# Mk3_Prototype.net
KiCad netlist of a schematic drawn in EAGLE
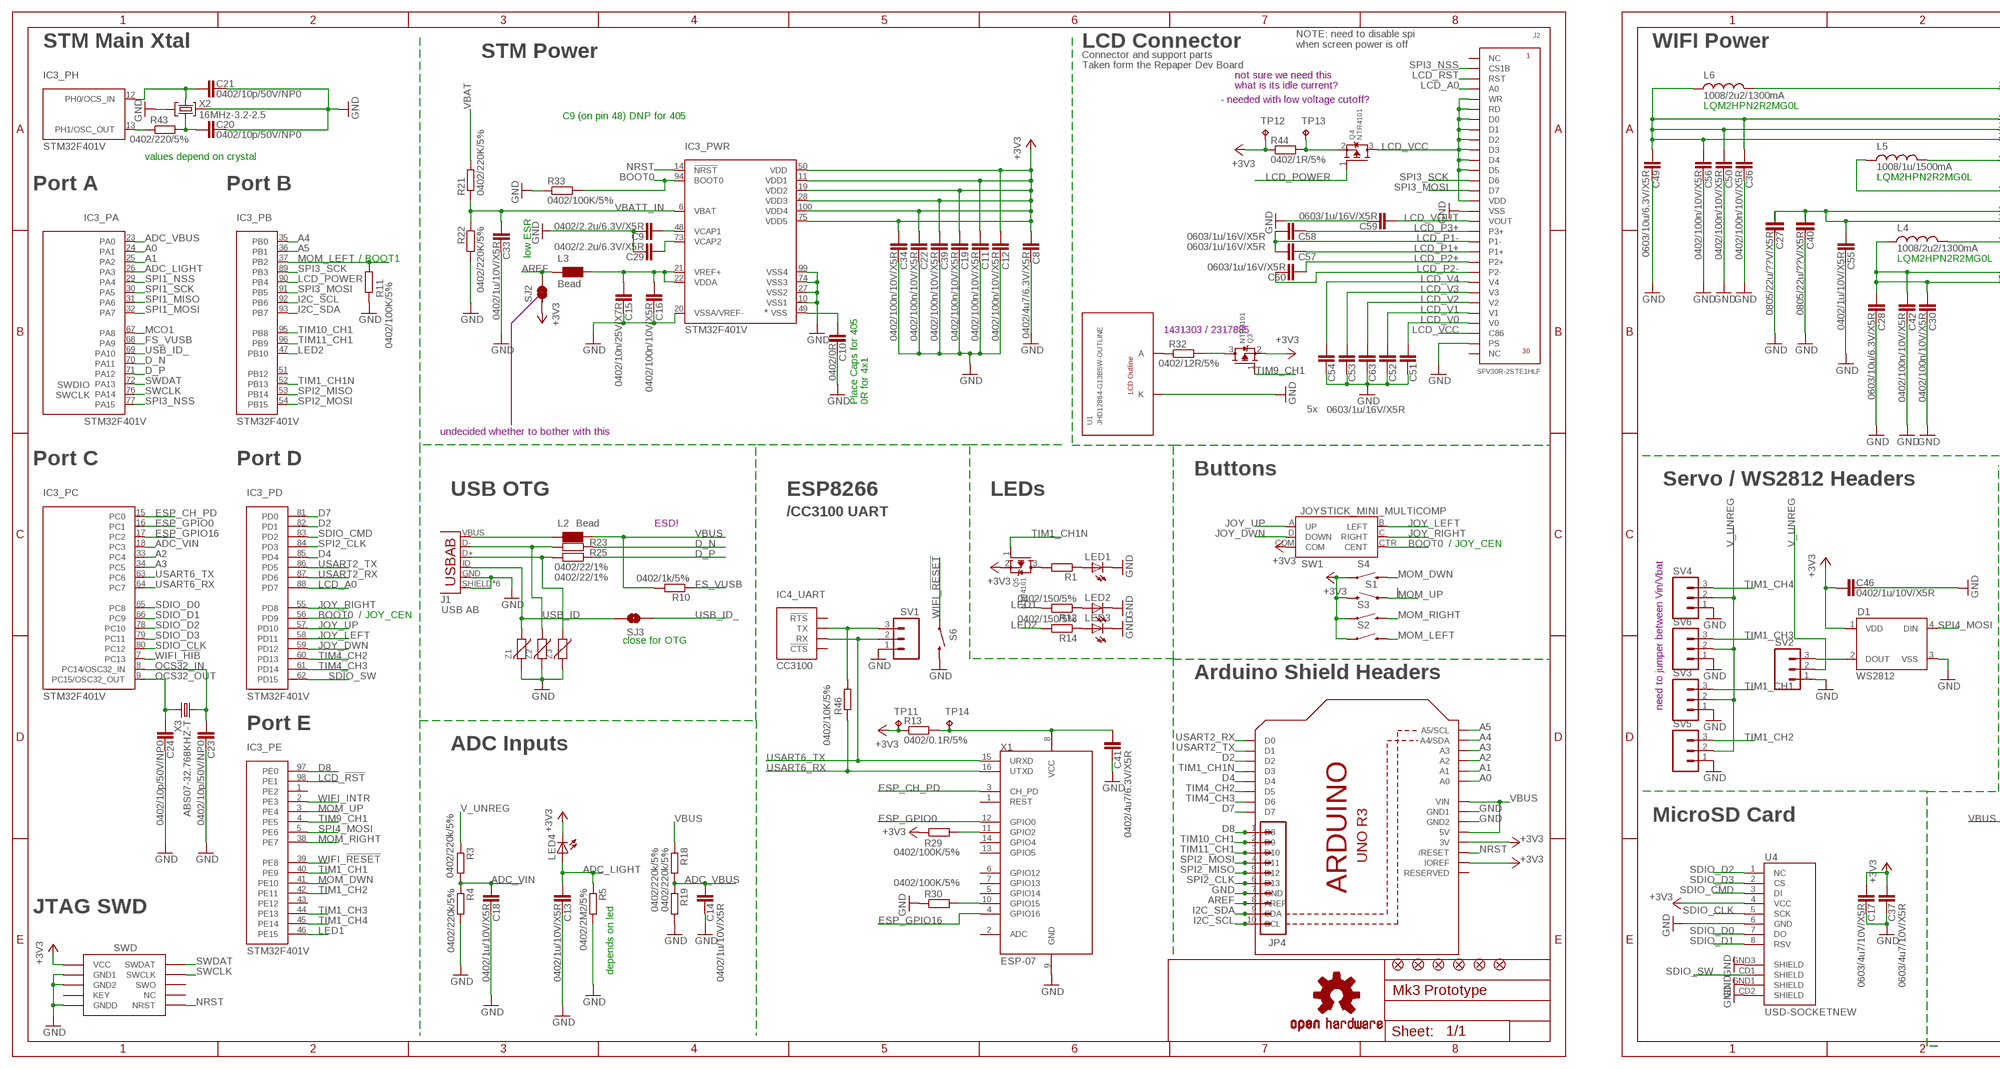
[diagram p0: schematic, sheet 1, part 1 of 2]
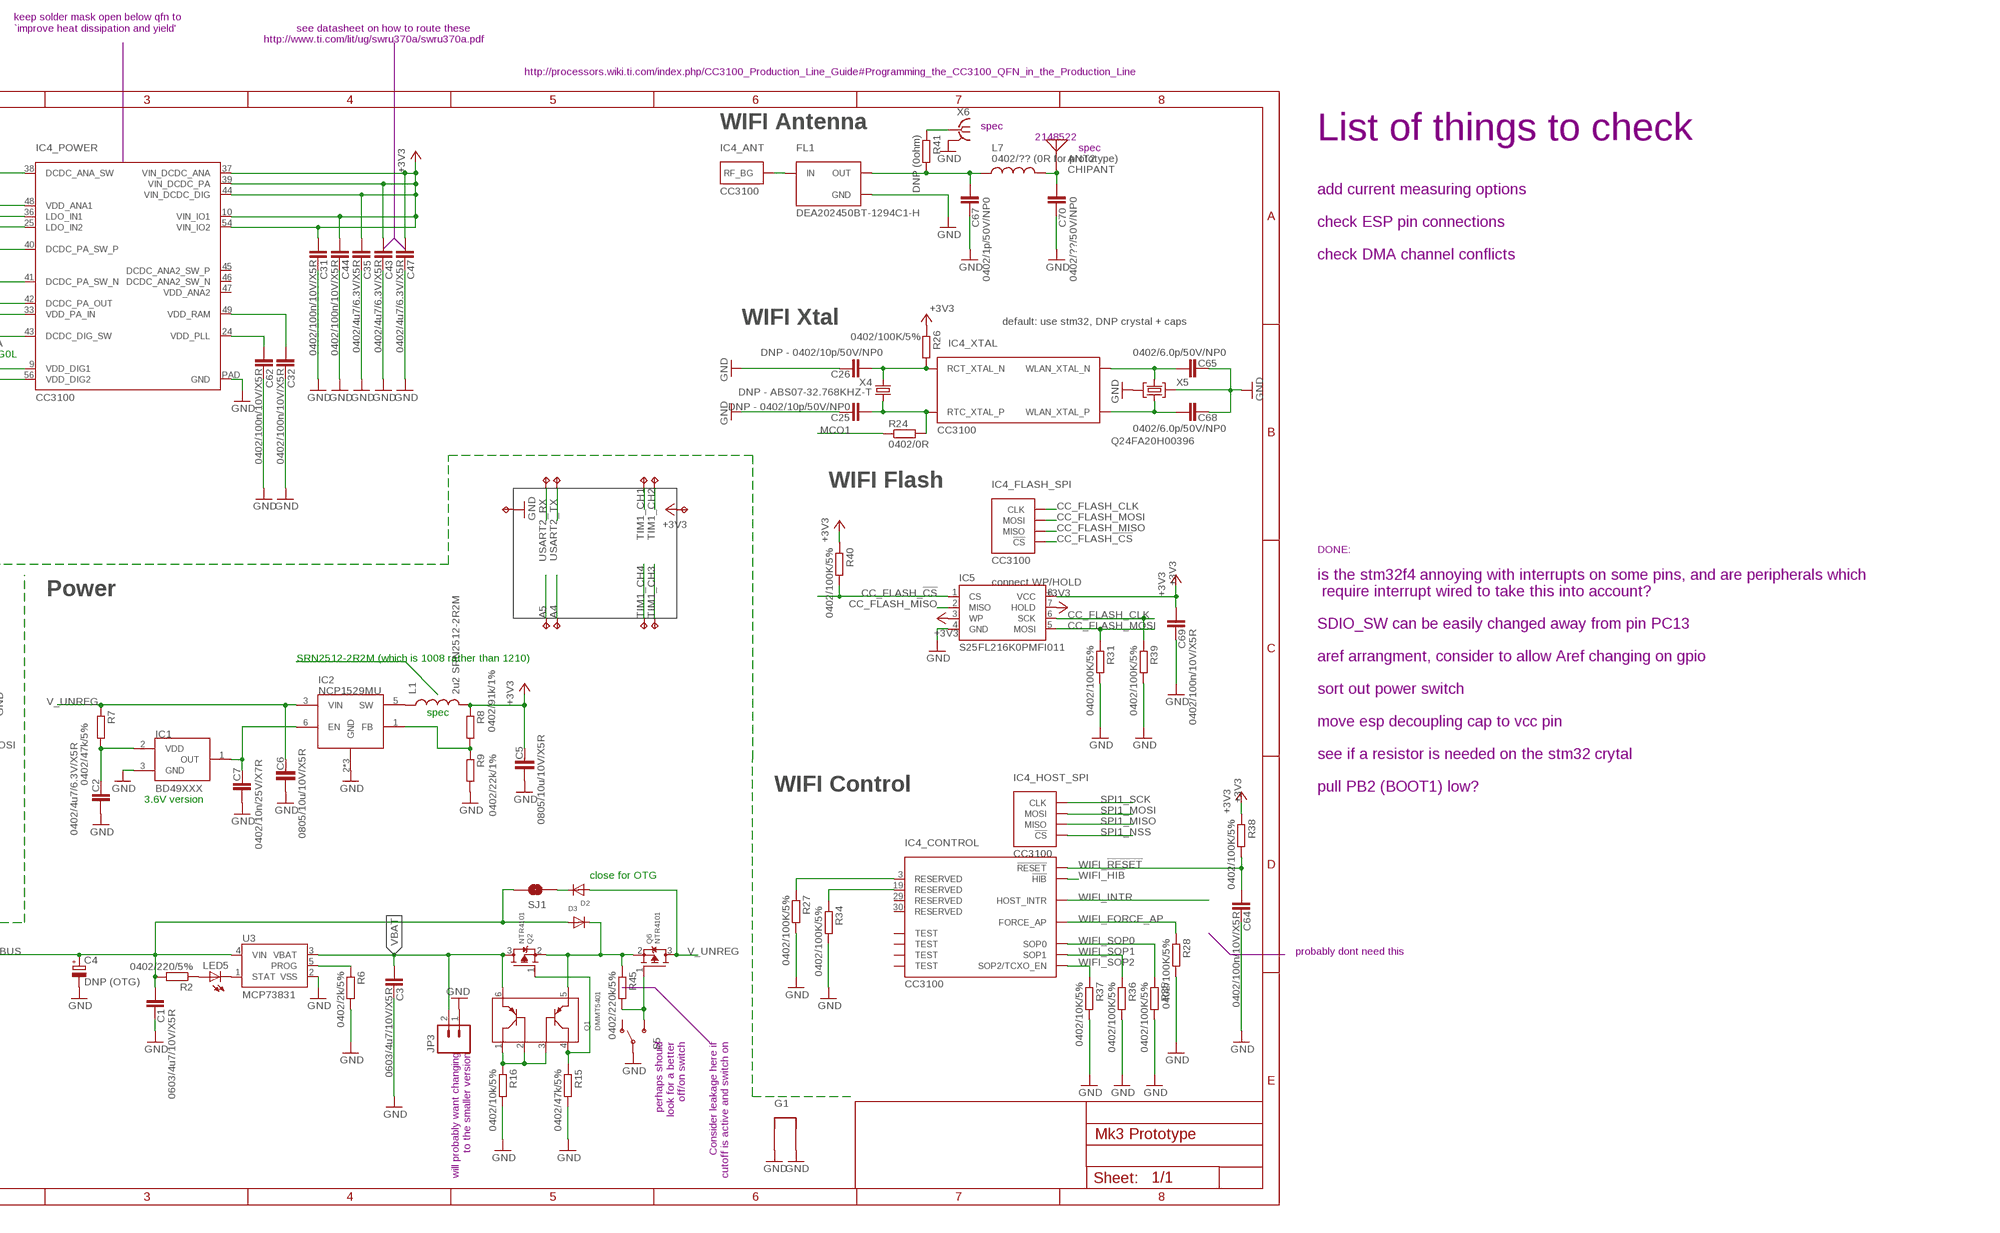
[diagram p1: schematic, sheet 1, part 2 of 2]

(export (version "E")
  (design (tool "Eeschema 10.0.6"))
  (components
    (comp (ref "ANT2")
      (value "CHIPANT")
      (footprint "eagle-import:2450AT42A100")
      (libsource (lib "eagle-import") (part "CHIPANT"))
    )
    (comp (ref "C1")
      (value "0603/4u7/10V/X5R")
      (footprint "eagle-import:C0805K")
      (libsource (lib "eagle-import") (part "C-EUC0805K"))
    )
    (comp (ref "C2")
      (value "0402/4u7/6.3V/X5R")
      (footprint "eagle-import:C0402-SMALLER")
      (libsource (lib "eagle-import") (part "C-EUC0402-SMALLER"))
    )
    (comp (ref "C3")
      (value "0603/4u7/10V/X5R")
      (footprint "eagle-import:C0603K-SMALL")
      (libsource (lib "eagle-import") (part "C-EUC0603K-SMALL"))
    )
    (comp (ref "C4")
      (value "DNP (OTG)")
      (footprint "eagle-import:E2,5-6")
      (libsource (lib "eagle-import") (part "CPOL-EUE2.5-6"))
    )
    (comp (ref "C5")
      (value "0805/10u/10V/X5R")
      (footprint "eagle-import:C0805-N")
      (libsource (lib "eagle-import") (part "CAPACITOR0805-N"))
    )
    (comp (ref "C6")
      (value "0805/10u/10V/X5R")
      (footprint "eagle-import:C0805-N")
      (libsource (lib "eagle-import") (part "CAPACITOR0805-N"))
    )
    (comp (ref "C7")
      (value "0402/10n/25V/X7R")
      (footprint "eagle-import:C0402-SMALLER")
      (libsource (lib "eagle-import") (part "C-EUC0402-SMALLER"))
    )
    (comp (ref "C8")
      (value "0402/4u7/6.3V/X5R")
      (footprint "eagle-import:C0402-SMALLER")
      (libsource (lib "eagle-import") (part "C-EUC0402-SMALLER"))
    )
    (comp (ref "C9")
      (value "0402/2.2u/6.3V/X5R")
      (footprint "eagle-import:C0402-SMALLER")
      (libsource (lib "eagle-import") (part "C-EUC0402-SMALLER"))
    )
    (comp (ref "C10")
      (value "0402/0R")
      (footprint "eagle-import:C0402-SMALLER")
      (libsource (lib "eagle-import") (part "C-EUC0402-SMALLER"))
    )
    (comp (ref "C11")
      (value "0402/100n/10V/X5R")
      (footprint "eagle-import:C0402-SMALLER")
      (libsource (lib "eagle-import") (part "C-EUC0402-SMALLER"))
    )
    (comp (ref "C12")
      (value "0402/100n/10V/X5R")
      (footprint "eagle-import:C0402-SMALLER")
      (libsource (lib "eagle-import") (part "C-EUC0402-SMALLER"))
    )
    (comp (ref "C13")
      (value "0402/1u/10V/X5R")
      (footprint "eagle-import:C0402-SMALLER")
      (libsource (lib "eagle-import") (part "C-EUC0402-SMALLER"))
    )
    (comp (ref "C14")
      (value "0402/1u/10V/X5R")
      (footprint "eagle-import:C0402-SMALLER")
      (libsource (lib "eagle-import") (part "C-EUC0402-SMALLER"))
    )
    (comp (ref "C15")
      (value "0402/10n/25V/X7R")
      (footprint "eagle-import:C0402-SMALLER")
      (libsource (lib "eagle-import") (part "C-EUC0402-SMALLER"))
    )
    (comp (ref "C16")
      (value "0402/100n/10V/X5R")
      (footprint "eagle-import:C0402-SMALLER")
      (libsource (lib "eagle-import") (part "C-EUC0402-SMALLER"))
    )
    (comp (ref "C17")
      (value "0603/4u7/10V/X5R")
      (footprint "eagle-import:C0603K-SMALL")
      (libsource (lib "eagle-import") (part "C-EUC0603K-SMALL"))
    )
    (comp (ref "C18")
      (value "0402/1u/10V/X5R")
      (footprint "eagle-import:C0402-SMALLER")
      (libsource (lib "eagle-import") (part "C-EUC0402-SMALLER"))
    )
    (comp (ref "C19")
      (value "0402/100n/10V/X5R")
      (footprint "eagle-import:C0402-SMALLER")
      (libsource (lib "eagle-import") (part "C-EUC0402-SMALLER"))
    )
    (comp (ref "C20")
      (value "0402/10p/50V/NP0")
      (footprint "eagle-import:C0402-SMALLER")
      (libsource (lib "eagle-import") (part "C-EUC0402-SMALLER"))
    )
    (comp (ref "C21")
      (value "0402/10p/50V/NP0")
      (footprint "eagle-import:C0402-SMALLER")
      (libsource (lib "eagle-import") (part "C-EUC0402-SMALLER"))
    )
    (comp (ref "C22")
      (value "0402/100n/10V/X5R")
      (footprint "eagle-import:C0402-SMALLER")
      (libsource (lib "eagle-import") (part "C-EUC0402-SMALLER"))
    )
    (comp (ref "C23")
      (value "0402/10p/50V/NP0")
      (footprint "eagle-import:C0402-SMALLER")
      (libsource (lib "eagle-import") (part "C-EUC0402-SMALLER"))
    )
    (comp (ref "C24")
      (value "0402/10p/50V/NP0")
      (footprint "eagle-import:C0402-SMALLER")
      (libsource (lib "eagle-import") (part "C-EUC0402-SMALLER"))
    )
    (comp (ref "C25")
      (value "DNP - 0402/10p/50V/NP0")
      (footprint "eagle-import:C0402-SMALLER")
      (libsource (lib "eagle-import") (part "C-EUC0402-SMALLER"))
    )
    (comp (ref "C26")
      (value "DNP - 0402/10p/50V/NP0")
      (footprint "eagle-import:C0402-SMALLER")
      (libsource (lib "eagle-import") (part "C-EUC0402-SMALLER"))
    )
    (comp (ref "C27")
      (value "0805/22u/??V/X5R")
      (footprint "eagle-import:C0805-N")
      (libsource (lib "eagle-import") (part "CAPACITOR0805-N"))
    )
    (comp (ref "C28")
      (value "0603/10u/6.3V/X5R")
      (footprint "eagle-import:C0603K-SMALL")
      (libsource (lib "eagle-import") (part "C-EUC0603K-SMALL"))
    )
    (comp (ref "C29")
      (value "0402/2.2u/6.3V/X5R")
      (footprint "eagle-import:C0402-SMALLER")
      (libsource (lib "eagle-import") (part "C-EUC0402-SMALLER"))
    )
    (comp (ref "C30")
      (value "0402/100n/10V/X5R")
      (footprint "eagle-import:C0402-SMALLER")
      (libsource (lib "eagle-import") (part "C-EUC0402-SMALLER"))
    )
    (comp (ref "C31")
      (value "0402/100n/10V/X5R")
      (footprint "eagle-import:C0402-SMALLER")
      (libsource (lib "eagle-import") (part "C-EUC0402-SMALLER"))
    )
    (comp (ref "C32")
      (value "0402/100n/10V/X5R")
      (footprint "eagle-import:C0402-SMALLER")
      (libsource (lib "eagle-import") (part "C-EUC0402-SMALLER"))
    )
    (comp (ref "C33")
      (value "0402/1u/10V/X5R")
      (footprint "eagle-import:C0402-SMALLER")
      (libsource (lib "eagle-import") (part "C-EUC0402-SMALLER"))
    )
    (comp (ref "C34")
      (value "0402/100n/10V/X5R")
      (footprint "eagle-import:C0402-SMALLER")
      (libsource (lib "eagle-import") (part "C-EUC0402-SMALLER"))
    )
    (comp (ref "C35")
      (value "0402/4u7/6.3V/X5R")
      (footprint "eagle-import:C0402-SMALLER")
      (libsource (lib "eagle-import") (part "C-EUC0402-SMALLER"))
    )
    (comp (ref "C36")
      (value "0402/100n/10V/X5R")
      (footprint "eagle-import:C0402-SMALLER")
      (libsource (lib "eagle-import") (part "C-EUC0402-SMALLER"))
    )
    (comp (ref "C37")
      (value "0603/4u7/10V/X5R")
      (footprint "eagle-import:C0603K-SMALL")
      (libsource (lib "eagle-import") (part "C-EUC0603K-SMALL"))
    )
    (comp (ref "C39")
      (value "0402/100n/10V/X5R")
      (footprint "eagle-import:C0402-SMALLER")
      (libsource (lib "eagle-import") (part "C-EUC0402-SMALLER"))
    )
    (comp (ref "C40")
      (value "0805/22u/??V/X5R")
      (footprint "eagle-import:C0805-N")
      (libsource (lib "eagle-import") (part "CAPACITOR0805-N"))
    )
    (comp (ref "C41")
      (value "0402/4u7/6.3V/X5R")
      (footprint "eagle-import:C0402-SMALLER")
      (libsource (lib "eagle-import") (part "C-EUC0402-SMALLER"))
    )
    (comp (ref "C42")
      (value "0402/100n/10V/X5R")
      (footprint "eagle-import:C0402-SMALLER")
      (libsource (lib "eagle-import") (part "C-EUC0402-SMALLER"))
    )
    (comp (ref "C43")
      (value "0402/4u7/6.3V/X5R")
      (footprint "eagle-import:C0402-SMALLER")
      (libsource (lib "eagle-import") (part "C-EUC0402-SMALLER"))
    )
    (comp (ref "C44")
      (value "0402/100n/10V/X5R")
      (footprint "eagle-import:C0402-SMALLER")
      (libsource (lib "eagle-import") (part "C-EUC0402-SMALLER"))
    )
    (comp (ref "C46")
      (value "0402/1u/10V/X5R")
      (footprint "eagle-import:C0402-SMALLER")
      (libsource (lib "eagle-import") (part "C-EUC0402-SMALLER"))
    )
    (comp (ref "C47")
      (value "0402/4u7/6.3V/X5R")
      (footprint "eagle-import:C0402-SMALLER")
      (libsource (lib "eagle-import") (part "C-EUC0402-SMALLER"))
    )
    (comp (ref "C49")
      (value "0603/10u/6.3V/X5R")
      (footprint "eagle-import:C0603K-SMALL")
      (libsource (lib "eagle-import") (part "C-EUC0603K-SMALL"))
    )
    (comp (ref "C50")
      (value "0402/100n/10V/X5R")
      (footprint "eagle-import:C0402-SMALLER")
      (libsource (lib "eagle-import") (part "C-EUC0402-SMALLER"))
    )
    (comp (ref "C51")
      (value "0603/1u/16V/X5R")
      (footprint "eagle-import:C0603K-SMALL")
      (libsource (lib "eagle-import") (part "C-EUC0603K-SMALL"))
    )
    (comp (ref "C52")
      (value "0603/1u/16V/X5R")
      (footprint "eagle-import:C0603K-SMALL")
      (libsource (lib "eagle-import") (part "C-EUC0603K-SMALL"))
    )
    (comp (ref "C53")
      (value "0603/1u/16V/X5R")
      (footprint "eagle-import:C0603K-SMALL")
      (libsource (lib "eagle-import") (part "C-EUC0603K-SMALL"))
    )
    (comp (ref "C54")
      (value "0603/1u/16V/X5R")
      (footprint "eagle-import:C0603K-SMALL")
      (libsource (lib "eagle-import") (part "C-EUC0603K-SMALL"))
    )
    (comp (ref "C55")
      (value "0402/1u/10V/X5R")
      (footprint "eagle-import:C0402-SMALLER")
      (libsource (lib "eagle-import") (part "C-EUC0402-SMALLER"))
    )
    (comp (ref "C56")
      (value "0402/100n/10V/X5R")
      (footprint "eagle-import:C0402-SMALLER")
      (libsource (lib "eagle-import") (part "C-EUC0402-SMALLER"))
    )
    (comp (ref "C57")
      (value "0603/1u/16V/X5R")
      (footprint "eagle-import:C0603K-SMALL")
      (libsource (lib "eagle-import") (part "C-EUC0603K-SMALL"))
    )
    (comp (ref "C58")
      (value "0603/1u/16V/X5R")
      (footprint "eagle-import:C0603K-SMALL")
      (libsource (lib "eagle-import") (part "C-EUC0603K-SMALL"))
    )
    (comp (ref "C59")
      (value "0603/1u/16V/X5R")
      (footprint "eagle-import:C0603K-SMALL")
      (libsource (lib "eagle-import") (part "C-EUC0603K-SMALL"))
    )
    (comp (ref "C60")
      (value "0603/1u/16V/X5R")
      (footprint "eagle-import:C0603K-SMALL")
      (libsource (lib "eagle-import") (part "C-EUC0603K-SMALL"))
    )
    (comp (ref "C62")
      (value "0402/100n/10V/X5R")
      (footprint "eagle-import:C0402-SMALLER")
      (libsource (lib "eagle-import") (part "C-EUC0402-SMALLER"))
    )
    (comp (ref "C63")
      (value "0603/1u/16V/X5R")
      (footprint "eagle-import:C0603K-SMALL")
      (libsource (lib "eagle-import") (part "C-EUC0603K-SMALL"))
    )
    (comp (ref "C64")
      (value "0402/100n/10V/X5R")
      (footprint "eagle-import:C0402-SMALLER")
      (libsource (lib "eagle-import") (part "C-EUC0402-SMALLER"))
    )
    (comp (ref "C65")
      (value "0402/6.0p/50V/NP0")
      (footprint "eagle-import:C0402-SMALLER")
      (libsource (lib "eagle-import") (part "C-EUC0402-SMALLER"))
    )
    (comp (ref "C67")
      (value "0402/1p/50V/NP0")
      (footprint "eagle-import:C0402-SMALLER")
      (libsource (lib "eagle-import") (part "C-EUC0402-SMALLER"))
    )
    (comp (ref "C68")
      (value "0402/6.0p/50V/NP0")
      (footprint "eagle-import:C0402-SMALLER")
      (libsource (lib "eagle-import") (part "C-EUC0402-SMALLER"))
    )
    (comp (ref "C69")
      (value "0402/100n/10V/X5R")
      (footprint "eagle-import:C0402-SMALLER")
      (libsource (lib "eagle-import") (part "C-EUC0402-SMALLER"))
    )
    (comp (ref "C70")
      (value "0402/??/50V/NP0")
      (footprint "eagle-import:C0402-SMALLER")
      (libsource (lib "eagle-import") (part "C-EUC0402-SMALLER"))
    )
    (comp (ref "D1")
      (value "WS2812B")
      (footprint "eagle-import:WS2812B")
      (libsource (lib "eagle-import") (part "WS2812B"))
    )
    (comp (ref "D2")
      (value "DIODESOD-323F")
      (footprint "eagle-import:SOD-323F")
      (libsource (lib "eagle-import") (part "DIODESOD-323F"))
    )
    (comp (ref "D3")
      (value "DIODESOD-323F")
      (footprint "eagle-import:SOD-323F")
      (libsource (lib "eagle-import") (part "DIODESOD-323F"))
    )
    (comp (ref "FID1")
      (value "FIDUCIAL1X2.5-STOP")
      (footprint "eagle-import:FIDUCIAL-1X2.5-STOP")
      (libsource (lib "eagle-import") (part "FIDUCIAL1X2.5-STOP"))
    )
    (comp (ref "FID2")
      (value "FIDUCIAL1X2.5-STOP")
      (footprint "eagle-import:FIDUCIAL-1X2.5-STOP")
      (libsource (lib "eagle-import") (part "FIDUCIAL1X2.5-STOP"))
    )
    (comp (ref "FID3")
      (value "FIDUCIAL1X2.5-STOP")
      (footprint "eagle-import:FIDUCIAL-1X2.5-STOP")
      (libsource (lib "eagle-import") (part "FIDUCIAL1X2.5-STOP"))
    )
    (comp (ref "FID4")
      (value "FIDUCIAL1X2.5-STOP")
      (footprint "eagle-import:FIDUCIAL-1X2.5-STOP")
      (libsource (lib "eagle-import") (part "FIDUCIAL1X2.5-STOP"))
    )
    (comp (ref "FID5")
      (value "FIDUCIAL1X2.5-STOP")
      (footprint "eagle-import:FIDUCIAL-1X2.5-STOP")
      (libsource (lib "eagle-import") (part "FIDUCIAL1X2.5-STOP"))
    )
    (comp (ref "FID6")
      (value "FIDUCIAL1X2.5-STOP")
      (footprint "eagle-import:FIDUCIAL-1X2.5-STOP")
      (libsource (lib "eagle-import") (part "FIDUCIAL1X2.5-STOP"))
    )
    (comp (ref "FL1")
      (value "DEA202450BT-1294C1-H")
      (footprint "eagle-import:DEA202450BT")
      (libsource (lib "eagle-import") (part "DEA202450BT-1294C1-H"))
    )
    (comp (ref "G1")
      (value "GND-LOOP")
      (footprint "eagle-import:GND-LOOP")
      (libsource (lib "eagle-import") (part "GND-LOOP"))
    )
    (comp (ref "IC1")
      (value "BD49XXX")
      (footprint "eagle-import:SSOP5")
      (libsource (lib "eagle-import") (part "BD49XXX"))
    )
    (comp (ref "IC2")
      (value "NCP1529MU")
      (footprint "eagle-import:DFN6")
      (libsource (lib "eagle-import") (part "NCP1529MU"))
    )
    (comp (ref "IC3")
      (value "STM32F401V")
      (footprint "eagle-import:TQFP100")
      (libsource (lib "eagle-import") (part "STM32F401V"))
    )
    (comp (ref "IC4")
      (value "CC3100")
      (footprint "eagle-import:VQFN-64")
      (libsource (lib "eagle-import") (part "CC3100"))
    )
    (comp (ref "IC5")
      (value "S25FL216K0PMFI011")
      (footprint "eagle-import:SO08-EIAJ")
      (libsource (lib "eagle-import") (part "SPI_FLASH-X25XXSMD1"))
    )
    (comp (ref "J1")
      (value "ZX62-AB-5PA(11)")
      (footprint "eagle-import:USB-AB-MICRO-SMD_LWK")
      (libsource (lib "eagle-import") (part "USB-AB-LWK"))
    )
    (comp (ref "J2")
      (value "SFV30R-2STE1HLF")
      (footprint "eagle-import:SFV30R-2STE1HLF")
      (libsource (lib "eagle-import") (part "JHD12863-G13BSW-CONNECTOR-SFV30R-2STE1HLF"))
    )
    (comp (ref "J3")
      (value "SWD_SHROUD")
      (footprint "eagle-import:SWD_PTH_SHROUD")
      (libsource (lib "eagle-import") (part "SWD_SHROUD"))
    )
    (comp (ref "JP3")
      (value "M02-JST-2MM-SMT")
      (footprint "eagle-import:JST-2-SMD")
      (libsource (lib "eagle-import") (part "M02-JST-2MM-SMT"))
    )
    (comp (ref "JP4")
      (value "M10NOSILK")
      (footprint "eagle-import:1X10-NOSILK")
      (libsource (lib "eagle-import") (part "M10NOSILK"))
    )
    (comp (ref "L1")
      (value "2u2 SRN2512-2R2M")
      (footprint "eagle-import:1210")
      (libsource (lib "eagle-import") (part "INDUCTOR1210"))
    )
    (comp (ref "L2")
      (value "Bead")
      (footprint "eagle-import:WUERTH-0805")
      (libsource (lib "eagle-import") (part "WE-CBF_0805"))
    )
    (comp (ref "L3")
      (value "Bead")
      (footprint "eagle-import:WUERTH-0805")
      (libsource (lib "eagle-import") (part "WE-CBF_0805"))
    )
    (comp (ref "L4")
      (value "1008/2u2/1300mA")
      (footprint "eagle-import:1008")
      (libsource (lib "eagle-import") (part "INDUCTOR1008"))
    )
    (comp (ref "L5")
      (value "1008/1u/1500mA")
      (footprint "eagle-import:1008")
      (libsource (lib "eagle-import") (part "INDUCTOR1008"))
    )
    (comp (ref "L6")
      (value "1008/2u2/1300mA")
      (footprint "eagle-import:1008")
      (libsource (lib "eagle-import") (part "INDUCTOR1008"))
    )
    (comp (ref "L7")
      (value "0402/?? (0R for prototype)")
      (footprint "eagle-import:L0402")
      (libsource (lib "eagle-import") (part "INDUCTOR-0402-NARROW"))
    )
    (comp (ref "LED1")
      (value "LED5MM")
      (footprint "eagle-import:LED5MM")
      (libsource (lib "eagle-import") (part "LED5MM"))
    )
    (comp (ref "LED2")
      (value "LED0603-CORRECT")
      (footprint "eagle-import:LED-0603-CORRECT")
      (libsource (lib "eagle-import") (part "LED0603-CORRECT"))
    )
    (comp (ref "LED3")
      (value "LED0603-CORRECT")
      (footprint "eagle-import:LED-0603-CORRECT")
      (libsource (lib "eagle-import") (part "LED0603-CORRECT"))
    )
    (comp (ref "LED4")
      (value "LED0603-CORRECT")
      (footprint "eagle-import:LED-0603-CORRECT")
      (libsource (lib "eagle-import") (part "LED0603-CORRECT"))
    )
    (comp (ref "LED5")
      (value "LED0603-CORRECT")
      (footprint "eagle-import:LED-0603-CORRECT")
      (libsource (lib "eagle-import") (part "LED0603-CORRECT"))
    )
    (comp (ref "LOGO1")
      (value "OSHW-LOGOM")
      (footprint "eagle-import:OSHW-LOGO-M")
      (libsource (lib "eagle-import") (part "OSHW-LOGOM"))
    )
    (comp (ref "Q1")
      (value "DMMT5401")
      (footprint "eagle-import:SOT26")
      (libsource (lib "eagle-import") (part "DMMT5401"))
    )
    (comp (ref "Q2")
      (value "NTR4101")
      (footprint "eagle-import:SOT23-R")
      (libsource (lib "eagle-import") (part "MOSFET-P-SOT23"))
    )
    (comp (ref "Q3")
      (value "NTR4101")
      (footprint "eagle-import:SOT23-R")
      (libsource (lib "eagle-import") (part "MOSFET-P-SOT23"))
    )
    (comp (ref "Q4")
      (value "NTR4101")
      (footprint "eagle-import:SOT23-R")
      (libsource (lib "eagle-import") (part "MOSFET-P-SOT23"))
    )
    (comp (ref "Q5")
      (value "NTR4101")
      (footprint "eagle-import:SOT23-R")
      (libsource (lib "eagle-import") (part "MOSFET-P-SOT23"))
    )
    (comp (ref "Q6")
      (value "NTR4101")
      (footprint "eagle-import:SOT23-R")
      (libsource (lib "eagle-import") (part "MOSFET-P-SOT23"))
    )
    (comp (ref "R1")
      (value "R-EU_0207/10")
      (footprint "eagle-import:0207_10")
      (libsource (lib "eagle-import") (part "R-EU_0207/10"))
    )
    (comp (ref "R2")
      (value "0402/220/5%")
      (footprint "eagle-import:R0402-SMALLER")
      (libsource (lib "eagle-import") (part "R-EU_R0402-SMALLER"))
    )
    (comp (ref "R3")
      (value "0402/220k/5%")
      (footprint "eagle-import:R0402-SMALLER")
      (libsource (lib "eagle-import") (part "R-EU_R0402-SMALLER"))
    )
    (comp (ref "R4")
      (value "0402/220k/5%")
      (footprint "eagle-import:R0402-SMALLER")
      (libsource (lib "eagle-import") (part "R-EU_R0402-SMALLER"))
    )
    (comp (ref "R5")
      (value "0402/2M2/5%")
      (footprint "eagle-import:R0402-SMALLER")
      (libsource (lib "eagle-import") (part "R-EU_R0402-SMALLER"))
    )
    (comp (ref "R6")
      (value "0402/2k/5%")
      (footprint "eagle-import:R0402-SMALLER")
      (libsource (lib "eagle-import") (part "R-EU_R0402-SMALLER"))
    )
    (comp (ref "R7")
      (value "0402/47k/5%")
      (footprint "eagle-import:R0402-SMALLER")
      (libsource (lib "eagle-import") (part "R-EU_R0402-SMALLER"))
    )
    (comp (ref "R8")
      (value "0402/91k/1%")
      (footprint "eagle-import:R0402-SMALLER")
      (libsource (lib "eagle-import") (part "R-EU_R0402-SMALLER"))
    )
    (comp (ref "R9")
      (value "0402/22k/1%")
      (footprint "eagle-import:R0402-SMALLER")
      (libsource (lib "eagle-import") (part "R-EU_R0402-SMALLER"))
    )
    (comp (ref "R10")
      (value "0402/1k/5%")
      (footprint "eagle-import:R0402-SMALLER")
      (libsource (lib "eagle-import") (part "R-EU_R0402-SMALLER"))
    )
    (comp (ref "R11")
      (value "0402/100K/5%")
      (footprint "eagle-import:R0402-SMALLER")
      (libsource (lib "eagle-import") (part "R-EU_R0402-SMALLER"))
    )
    (comp (ref "R12")
      (value "0402/150/5%")
      (footprint "eagle-import:R0402-SMALLER")
      (libsource (lib "eagle-import") (part "R-EU_R0402-SMALLER"))
    )
    (comp (ref "R13")
      (value "0402/0.1R/5%")
      (footprint "eagle-import:R0402-SMALLER")
      (libsource (lib "eagle-import") (part "R-EU_R0402-SMALLER"))
    )
    (comp (ref "R14")
      (value "0402/150/5%")
      (footprint "eagle-import:R0402-SMALLER")
      (libsource (lib "eagle-import") (part "R-EU_R0402-SMALLER"))
    )
    (comp (ref "R15")
      (value "0402/47k/5%")
      (footprint "eagle-import:R0402-SMALLER")
      (libsource (lib "eagle-import") (part "R-EU_R0402-SMALLER"))
    )
    (comp (ref "R16")
      (value "0402/10k/5%")
      (footprint "eagle-import:R0402-SMALLER")
      (libsource (lib "eagle-import") (part "R-EU_R0402-SMALLER"))
    )
    (comp (ref "R18")
      (value "0402/220k/5%")
      (footprint "eagle-import:R0402-SMALLER")
      (libsource (lib "eagle-import") (part "R-EU_R0402-SMALLER"))
    )
    (comp (ref "R19")
      (value "0402/220k/5%")
      (footprint "eagle-import:R0402-SMALLER")
      (libsource (lib "eagle-import") (part "R-EU_R0402-SMALLER"))
    )
    (comp (ref "R21")
      (value "0402/220K/5%")
      (footprint "eagle-import:R0402-SMALLER")
      (libsource (lib "eagle-import") (part "R-EU_R0402-SMALLER"))
    )
    (comp (ref "R22")
      (value "0402/220K/5%")
      (footprint "eagle-import:R0402-SMALLER")
      (libsource (lib "eagle-import") (part "R-EU_R0402-SMALLER"))
    )
    (comp (ref "R23")
      (value "0402/22/1%")
      (footprint "eagle-import:R0402-SMALLER")
      (libsource (lib "eagle-import") (part "R-EU_R0402-SMALLER"))
    )
    (comp (ref "R24")
      (value "0402/0R")
      (footprint "eagle-import:R0402-SMALLER")
      (libsource (lib "eagle-import") (part "R-EU_R0402-SMALLER"))
    )
    (comp (ref "R25")
      (value "0402/22/1%")
      (footprint "eagle-import:R0402-SMALLER")
      (libsource (lib "eagle-import") (part "R-EU_R0402-SMALLER"))
    )
    (comp (ref "R26")
      (value "0402/100K/5%")
      (footprint "eagle-import:R0402-SMALLER")
      (libsource (lib "eagle-import") (part "R-EU_R0402-SMALLER"))
    )
    (comp (ref "R27")
      (value "0402/100K/5%")
      (footprint "eagle-import:R0402-SMALLER")
      (libsource (lib "eagle-import") (part "R-EU_R0402-SMALLER"))
    )
    (comp (ref "R28")
      (value "0402/100K/5%")
      (footprint "eagle-import:R0402-SMALLER")
      (libsource (lib "eagle-import") (part "R-EU_R0402-SMALLER"))
    )
    (comp (ref "R29")
      (value "0402/100K/5%")
      (footprint "eagle-import:R0402-SMALLER")
      (libsource (lib "eagle-import") (part "R-EU_R0402-SMALLER"))
    )
    (comp (ref "R30")
      (value "0402/100K/5%")
      (footprint "eagle-import:R0402-SMALLER")
      (libsource (lib "eagle-import") (part "R-EU_R0402-SMALLER"))
    )
    (comp (ref "R31")
      (value "0402/100K/5%")
      (footprint "eagle-import:R0402-SMALLER")
      (libsource (lib "eagle-import") (part "R-EU_R0402-SMALLER"))
    )
    (comp (ref "R32")
      (value "0402/12R/5%")
      (footprint "eagle-import:R0402-SMALLER")
      (libsource (lib "eagle-import") (part "R-EU_R0402-SMALLER"))
    )
    (comp (ref "R33")
      (value "0402/100K/5%")
      (footprint "eagle-import:R0402-SMALLER")
      (libsource (lib "eagle-import") (part "R-EU_R0402-SMALLER"))
    )
    (comp (ref "R34")
      (value "0402/100K/5%")
      (footprint "eagle-import:R0402-SMALLER")
      (libsource (lib "eagle-import") (part "R-EU_R0402-SMALLER"))
    )
    (comp (ref "R35")
      (value "0402/100K/5%")
      (footprint "eagle-import:R0402-SMALLER")
      (libsource (lib "eagle-import") (part "R-EU_R0402-SMALLER"))
    )
    (comp (ref "R36")
      (value "0402/100K/5%")
      (footprint "eagle-import:R0402-SMALLER")
      (libsource (lib "eagle-import") (part "R-EU_R0402-SMALLER"))
    )
    (comp (ref "R37")
      (value "0402/10K/5%")
      (footprint "eagle-import:R0402-SMALLER")
      (libsource (lib "eagle-import") (part "R-EU_R0402-SMALLER"))
    )
    (comp (ref "R38")
      (value "0402/100K/5%")
      (footprint "eagle-import:R0402-SMALLER")
      (libsource (lib "eagle-import") (part "R-EU_R0402-SMALLER"))
    )
    (comp (ref "R39")
      (value "0402/100K/5%")
      (footprint "eagle-import:R0402-SMALLER")
      (libsource (lib "eagle-import") (part "R-EU_R0402-SMALLER"))
    )
    (comp (ref "R40")
      (value "0402/100K/5%")
      (footprint "eagle-import:R0402-SMALLER")
      (libsource (lib "eagle-import") (part "R-EU_R0402-SMALLER"))
    )
    (comp (ref "R41")
      (value "DNP (0ohm)")
      (footprint "eagle-import:R0402-SMALLER")
      (libsource (lib "eagle-import") (part "R-EU_R0402-SMALLER"))
    )
    (comp (ref "R43")
      (value "0402/220/5%")
      (footprint "eagle-import:R0402-SMALLER")
      (libsource (lib "eagle-import") (part "R-EU_R0402-SMALLER"))
    )
    (comp (ref "R44")
      (value "0402/1R/5%")
      (footprint "eagle-import:R0402-SMALLER")
      (libsource (lib "eagle-import") (part "R-EU_R0402-SMALLER"))
    )
    (comp (ref "R45")
      (value "0402/220k/5%")
      (footprint "eagle-import:R0402-SMALLER")
      (libsource (lib "eagle-import") (part "R-EU_R0402-SMALLER"))
    )
    (comp (ref "R46")
      (value "0402/10K/5%")
      (footprint "eagle-import:R0402-SMALLER")
      (libsource (lib "eagle-import") (part "R-EU_R0402-SMALLER"))
    )
    (comp (ref "S1")
      (value "SWITCH-MOMENTARY-2")
      (footprint "eagle-import:TACTILE_SWITCH_TALL")
      (libsource (lib "eagle-import") (part "SWITCH-MOMENTARY-2"))
    )
    (comp (ref "S2")
      (value "SWITCH-MOMENTARY-2")
      (footprint "eagle-import:TACTILE_SWITCH_TALL")
      (libsource (lib "eagle-import") (part "SWITCH-MOMENTARY-2"))
    )
    (comp (ref "S3")
      (value "SWITCH-MOMENTARY-2")
      (footprint "eagle-import:TACTILE_SWITCH_TALL")
      (libsource (lib "eagle-import") (part "SWITCH-MOMENTARY-2"))
    )
    (comp (ref "S4")
      (value "SWITCH-MOMENTARY-2")
      (footprint "eagle-import:TACTILE_SWITCH_TALL")
      (libsource (lib "eagle-import") (part "SWITCH-MOMENTARY-2"))
    )
    (comp (ref "S5")
      (value "SWITCH-SPST-SMD-A")
      (footprint "eagle-import:SWITCH-SPST-SMD-A")
      (libsource (lib "eagle-import") (part "SWITCH-SPST-SMD-A"))
    )
    (comp (ref "S6")
      (value "SWITCH-MOMENTARY-2SMD-1101NE")
      (footprint "eagle-import:TACTILE-SWITCH-1101NE")
      (libsource (lib "eagle-import") (part "SWITCH-MOMENTARY-2SMD-1101NE"))
    )
    (comp (ref "SJ1")
      (value "JUMPER-PAD-2-NOYES_SILK")
      (footprint "eagle-import:PAD-JUMPER-2-NO_YES_SILK")
      (libsource (lib "eagle-import") (part "JUMPER-PAD-2-NOYES_SILK"))
    )
    (comp (ref "SJ2")
      (value "SOLDERJUMPERTRACE")
      (footprint "eagle-import:SJ_2S-TRACE")
      (libsource (lib "eagle-import") (part "SOLDERJUMPERTRACE"))
    )
    (comp (ref "SJ3")
      (value "JUMPER-PAD-2-NOYES_SILK")
      (footprint "eagle-import:PAD-JUMPER-2-NO_YES_SILK")
      (libsource (lib "eagle-import") (part "JUMPER-PAD-2-NOYES_SILK"))
    )
    (comp (ref "SV1")
      (value "M03PTH")
      (footprint "eagle-import:1X03")
      (libsource (lib "eagle-import") (part "M03PTH"))
    )
    (comp (ref "SV2")
      (value "M03PTH")
      (footprint "eagle-import:1X03")
      (libsource (lib "eagle-import") (part "M03PTH"))
    )
    (comp (ref "SV3")
      (value "M03PTH")
      (footprint "eagle-import:1X03")
      (libsource (lib "eagle-import") (part "M03PTH"))
    )
    (comp (ref "SV4")
      (value "M03PTH")
      (footprint "eagle-import:1X03")
      (libsource (lib "eagle-import") (part "M03PTH"))
    )
    (comp (ref "SV5")
      (value "M03PTH")
      (footprint "eagle-import:1X03")
      (libsource (lib "eagle-import") (part "M03PTH"))
    )
    (comp (ref "SV6")
      (value "M03PTH")
      (footprint "eagle-import:1X03")
      (libsource (lib "eagle-import") (part "M03PTH"))
    )
    (comp (ref "SW1")
      (value "JOYSTICK_MINI_MULTICOMP")
      (footprint "eagle-import:JOYSTICK_MULTICOMP")
      (libsource (lib "eagle-import") (part "JOYSTICK_MINI_MULTICOMP"))
    )
    (comp (ref "TP1")
      (value "TP4MM")
      (footprint "eagle-import:4MMEDGE")
      (libsource (lib "eagle-import") (part "TP4MM"))
    )
    (comp (ref "TP2")
      (value "TP4MM")
      (footprint "eagle-import:4MMEDGE")
      (libsource (lib "eagle-import") (part "TP4MM"))
    )
    (comp (ref "TP3")
      (value "TP4MM")
      (footprint "eagle-import:4MMEDGE")
      (libsource (lib "eagle-import") (part "TP4MM"))
    )
    (comp (ref "TP4")
      (value "TP4MM")
      (footprint "eagle-import:4MMEDGE")
      (libsource (lib "eagle-import") (part "TP4MM"))
    )
    (comp (ref "TP5")
      (value "TP4MM")
      (footprint "eagle-import:4MMEDGE")
      (libsource (lib "eagle-import") (part "TP4MM"))
    )
    (comp (ref "TP6")
      (value "TP4MM")
      (footprint "eagle-import:4MMEDGE")
      (libsource (lib "eagle-import") (part "TP4MM"))
    )
    (comp (ref "TP7")
      (value "TP4MM")
      (footprint "eagle-import:4MMEDGE")
      (libsource (lib "eagle-import") (part "TP4MM"))
    )
    (comp (ref "TP8")
      (value "TP4MM")
      (footprint "eagle-import:4MMEDGE")
      (libsource (lib "eagle-import") (part "TP4MM"))
    )
    (comp (ref "TP9")
      (value "TP4MM")
      (footprint "eagle-import:4MMEDGE")
      (libsource (lib "eagle-import") (part "TP4MM"))
    )
    (comp (ref "TP10")
      (value "TP4MM")
      (footprint "eagle-import:4MMEDGE")
      (libsource (lib "eagle-import") (part "TP4MM"))
    )
    (comp (ref "TP11")
      (value "TPB1,27")
      (footprint "eagle-import:B1,27")
      (libsource (lib "eagle-import") (part "TPB1,27"))
    )
    (comp (ref "TP12")
      (value "TPB1,27")
      (footprint "eagle-import:B1,27")
      (libsource (lib "eagle-import") (part "TPB1,27"))
    )
    (comp (ref "TP13")
      (value "TPB1,27")
      (footprint "eagle-import:B1,27")
      (libsource (lib "eagle-import") (part "TPB1,27"))
    )
    (comp (ref "TP14")
      (value "TPB1,27")
      (footprint "eagle-import:B1,27")
      (libsource (lib "eagle-import") (part "TPB1,27"))
    )
    (comp (ref "U1")
      (value "JHD12864-G13BSW-OUTLINE")
      (footprint "eagle-import:JHD12864-G13BSW-OUTLINE")
      (libsource (lib "eagle-import") (part "JHD12864-G13BSW-OUTLINE"))
    )
    (comp (ref "U2")
      (value "ARDUINOR3-NODIM")
      (footprint "eagle-import:ARDUINOR3-NODIM")
      (libsource (lib "eagle-import") (part "ARDUINOR3-NODIM"))
    )
    (comp (ref "U3")
      (value "MCP73831")
      (footprint "eagle-import:SOT23-5")
      (libsource (lib "eagle-import") (part "MCP73831"))
    )
    (comp (ref "U4")
      (value "USD-SOCKETNEW")
      (footprint "eagle-import:MICRO-SD-SOCKET-PP")
      (libsource (lib "eagle-import") (part "USD-SOCKETNEW"))
    )
    (comp (ref "X1")
      (value "ESP-07")
      (footprint "eagle-import:ESP-07")
      (libsource (lib "eagle-import") (part "ESP-07"))
    )
    (comp (ref "X2")
      (value "16MHz-3.2-2.5")
      (footprint "eagle-import:CRYSTAL-3.2-2.5")
      (libsource (lib "eagle-import") (part "CRYSTAL-3.2-2.5"))
    )
    (comp (ref "X3")
      (value "ABS07-32.768KHZ-T")
      (footprint "eagle-import:RESONATOR_EPSON_FC_145")
      (libsource (lib "eagle-import") (part "RESONATOR_EPSON_FC_145"))
    )
    (comp (ref "X4")
      (value "DNP - ABS07-32.768KHZ-T")
      (footprint "eagle-import:RESONATOR_EPSON_FC_145")
      (libsource (lib "eagle-import") (part "RESONATOR_EPSON_FC_145"))
    )
    (comp (ref "X5")
      (value "Q24FA20H00396")
      (footprint "eagle-import:CRYSTAL-2.5X2.0")
      (libsource (lib "eagle-import") (part "CRYSTAL-2.5X2.0"))
    )
    (comp (ref "X6")
      (value "MC-921")
      (footprint "eagle-import:MC-921")
      (libsource (lib "eagle-import") (part "MC-921"))
    )
    (comp (ref "Z1")
      (value "VARISTORCN0603")
      (footprint "eagle-import:CT_CN0603")
      (libsource (lib "eagle-import") (part "VARISTORCN0603"))
    )
    (comp (ref "Z2")
      (value "VARISTORCN0603")
      (footprint "eagle-import:CT_CN0603")
      (libsource (lib "eagle-import") (part "VARISTORCN0603"))
    )
    (comp (ref "Z3")
      (value "VARISTORCN0603")
      (footprint "eagle-import:CT_CN0603")
      (libsource (lib "eagle-import") (part "VARISTORCN0603"))
    )
  )
  (nets
    (net (code "1") (name "+3V3") (class "Default")
      (node (ref "C11") (pin "2") (pinfunction "2_2") (pintype "passive"))
      (node (ref "C12") (pin "2") (pinfunction "2_2") (pintype "passive"))
      (node (ref "C17") (pin "2") (pinfunction "2_2") (pintype "passive"))
      (node (ref "C19") (pin "2") (pinfunction "2_2") (pintype "passive"))
      (node (ref "C22") (pin "2") (pinfunction "2_2") (pintype "passive"))
      (node (ref "C31") (pin "2") (pinfunction "2_2") (pintype "passive"))
      (node (ref "C34") (pin "2") (pinfunction "2_2") (pintype "passive"))
      (node (ref "C35") (pin "2") (pinfunction "2_2") (pintype "passive"))
      (node (ref "C37") (pin "2") (pinfunction "2_2") (pintype "passive"))
      (node (ref "C39") (pin "2") (pinfunction "2_2") (pintype "passive"))
      (node (ref "C43") (pin "2") (pinfunction "2_2") (pintype "passive"))
      (node (ref "C44") (pin "2") (pinfunction "2_2") (pintype "passive"))
      (node (ref "C46") (pin "2") (pinfunction "2_2") (pintype "passive"))
      (node (ref "C47") (pin "2") (pinfunction "2_2") (pintype "passive"))
      (node (ref "C5") (pin "1") (pinfunction "1_1") (pintype "passive"))
      (node (ref "C69") (pin "2") (pinfunction "2_2") (pintype "passive"))
      (node (ref "C8") (pin "2") (pinfunction "2_2") (pintype "passive"))
      (node (ref "D1") (pin "1") (pinfunction "VDD_1") (pintype "power_in"))
      (node (ref "IC3") (pin "100") (pinfunction "VDD4_100") (pintype "bidirectional"))
      (node (ref "IC3") (pin "11") (pinfunction "VDD1_11") (pintype "bidirectional"))
      (node (ref "IC3") (pin "19") (pinfunction "VDD2_19") (pintype "bidirectional"))
      (node (ref "IC3") (pin "28") (pinfunction "VDD3_28") (pintype "bidirectional"))
      (node (ref "IC3") (pin "50") (pinfunction "VDD_50") (pintype "bidirectional"))
      (node (ref "IC3") (pin "75") (pinfunction "VDD5_75") (pintype "bidirectional"))
      (node (ref "IC4") (pin "10") (pinfunction "VIN_IO1_10") (pintype "bidirectional"))
      (node (ref "IC4") (pin "37") (pinfunction "VIN_DCDC_ANA_37") (pintype "bidirectional"))
      (node (ref "IC4") (pin "39") (pinfunction "VIN_DCDC_PA_39") (pintype "bidirectional"))
      (node (ref "IC4") (pin "44") (pinfunction "VIN_DCDC_DIG_44") (pintype "bidirectional"))
      (node (ref "IC4") (pin "54") (pinfunction "VIN_IO2_54") (pintype "bidirectional"))
      (node (ref "IC5") (pin "3") (pinfunction "WP_3") (pintype "bidirectional"))
      (node (ref "IC5") (pin "7") (pinfunction "HOLD_7") (pintype "bidirectional"))
      (node (ref "IC5") (pin "8") (pinfunction "VCC_8") (pintype "bidirectional"))
      (node (ref "J3") (pin "1") (pinfunction "VCC_1") (pintype "power_in"))
      (node (ref "L1") (pin "2") (pinfunction "2_2") (pintype "passive"))
      (node (ref "LED4") (pin "C") (pinfunction "C_C") (pintype "passive"))
      (node (ref "Q3") (pin "2") (pinfunction "S_2") (pintype "bidirectional"))
      (node (ref "Q5") (pin "2") (pinfunction "S_2") (pintype "bidirectional"))
      (node (ref "R13") (pin "1") (pinfunction "1_1") (pintype "passive"))
      (node (ref "R26") (pin "1") (pinfunction "1_1") (pintype "passive"))
      (node (ref "R29") (pin "1") (pinfunction "1_1") (pintype "passive"))
      (node (ref "R38") (pin "1") (pinfunction "1_1") (pintype "passive"))
      (node (ref "R40") (pin "1") (pinfunction "1_1") (pintype "passive"))
      (node (ref "R44") (pin "1") (pinfunction "1_1") (pintype "passive"))
      (node (ref "R8") (pin "1") (pinfunction "1_1") (pintype "passive"))
      (node (ref "S1") (pin "B2") (pinfunction "2_B2") (pintype "passive"))
      (node (ref "S2") (pin "A2") (pinfunction "1_A2") (pintype "passive"))
      (node (ref "S3") (pin "A2") (pinfunction "1_A2") (pintype "passive"))
      (node (ref "S4") (pin "A2") (pinfunction "1_A2") (pintype "passive"))
      (node (ref "SJ2") (pin "1") (pinfunction "1_1") (pintype "passive"))
      (node (ref "SW1") (pin "COM") (pinfunction "COM_COM") (pintype "bidirectional"))
      (node (ref "TP11") (pin "TP") (pinfunction "TP_TP") (pintype "input"))
      (node (ref "TP12") (pin "TP") (pinfunction "TP_TP") (pintype "input"))
      (node (ref "TP6") (pin "P$1") (pinfunction "TP_P$1") (pintype "input"))
      (node (ref "U2") (pin "3V") (pinfunction "3V_3V") (pintype "power_in"))
      (node (ref "U2") (pin "IOREF") (pinfunction "IOREF_IOREF") (pintype "output"))
      (node (ref "U4") (pin "4") (pinfunction "VCC_4") (pintype "bidirectional"))
    )
    (net (code "2") (name "/A0") (class "Default")
      (node (ref "IC3") (pin "24") (pinfunction "PA1_24") (pintype "bidirectional"))
      (node (ref "U2") (pin "A0") (pinfunction "A0_A0") (pintype "bidirectional"))
    )
    (net (code "3") (name "/A1") (class "Default")
      (node (ref "IC3") (pin "25") (pinfunction "PA2_25") (pintype "bidirectional"))
      (node (ref "U2") (pin "A1") (pinfunction "A1_A1") (pintype "bidirectional"))
    )
    (net (code "4") (name "/A2") (class "Default")
      (node (ref "IC3") (pin "33") (pinfunction "PC4_33") (pintype "bidirectional"))
      (node (ref "U2") (pin "A2") (pinfunction "A2_A2") (pintype "bidirectional"))
    )
    (net (code "5") (name "/A3") (class "Default")
      (node (ref "IC3") (pin "34") (pinfunction "PC5_34") (pintype "bidirectional"))
      (node (ref "U2") (pin "A3") (pinfunction "A3_A3") (pintype "bidirectional"))
    )
    (net (code "6") (name "/A4") (class "Default")
      (node (ref "IC3") (pin "35") (pinfunction "PB0_35") (pintype "bidirectional"))
      (node (ref "TP8") (pin "P$1") (pinfunction "TP_P$1") (pintype "input"))
      (node (ref "U2") (pin "A4") (pinfunction "A4/SDA_A4") (pintype "bidirectional"))
    )
    (net (code "7") (name "/A5") (class "Default")
      (node (ref "IC3") (pin "36") (pinfunction "PB1_36") (pintype "bidirectional"))
      (node (ref "TP7") (pin "P$1") (pinfunction "TP_P$1") (pintype "input"))
      (node (ref "U2") (pin "A5") (pinfunction "A5/SCL_A5") (pintype "bidirectional"))
    )
    (net (code "8") (name "/ADC_LIGHT") (class "Default")
      (node (ref "C13") (pin "2") (pinfunction "2_2") (pintype "passive"))
      (node (ref "IC3") (pin "26") (pinfunction "PA3_26") (pintype "bidirectional"))
      (node (ref "LED4") (pin "A") (pinfunction "A_A") (pintype "passive"))
      (node (ref "R5") (pin "1") (pinfunction "1_1") (pintype "passive"))
    )
    (net (code "9") (name "/ADC_VBUS") (class "Default")
      (node (ref "C14") (pin "2") (pinfunction "2_2") (pintype "passive"))
      (node (ref "IC3") (pin "23") (pinfunction "PA0_23") (pintype "bidirectional"))
      (node (ref "R18") (pin "2") (pinfunction "2_2") (pintype "passive"))
      (node (ref "R19") (pin "1") (pinfunction "1_1") (pintype "passive"))
    )
    (net (code "10") (name "/ADC_VIN") (class "Default")
      (node (ref "C18") (pin "2") (pinfunction "2_2") (pintype "passive"))
      (node (ref "IC3") (pin "18") (pinfunction "PC3_18") (pintype "bidirectional"))
      (node (ref "R3") (pin "2") (pinfunction "2_2") (pintype "passive"))
      (node (ref "R4") (pin "1") (pinfunction "1_1") (pintype "passive"))
    )
    (net (code "11") (name "/AREF") (class "Default")
      (node (ref "JP4") (pin "8") (pinfunction "8_8") (pintype "passive"))
      (node (ref "L3") (pin "1") (pinfunction "1_1") (pintype "passive"))
      (node (ref "SJ2") (pin "2") (pinfunction "2_2") (pintype "passive"))
      (node (ref "U2") (pin "AREF") (pinfunction "AREF_AREF") (pintype "bidirectional"))
    )
    (net (code "12") (name "/BOOT0") (class "Default")
      (node (ref "IC3") (pin "56") (pinfunction "PD9_56") (pintype "bidirectional"))
      (node (ref "IC3") (pin "94") (pinfunction "BOOT0_94") (pintype "bidirectional"))
      (node (ref "R33") (pin "2") (pinfunction "2_2") (pintype "passive"))
      (node (ref "SW1") (pin "CTR") (pinfunction "CENT_CTR") (pintype "bidirectional"))
    )
    (net (code "13") (name "/CC_FLASH_CLK") (class "Default")
      (node (ref "IC4") (pin "11") (pinfunction "CLK_11") (pintype "bidirectional"))
      (node (ref "IC5") (pin "6") (pinfunction "SCK_6") (pintype "bidirectional"))
      (node (ref "R39") (pin "1") (pinfunction "1_1") (pintype "passive"))
    )
    (net (code "14") (name "/CC_FLASH_MISO") (class "Default")
      (node (ref "IC4") (pin "13") (pinfunction "MISO_13") (pintype "bidirectional"))
      (node (ref "IC5") (pin "2") (pinfunction "MISO_2") (pintype "bidirectional"))
    )
    (net (code "15") (name "/CC_FLASH_MOSI") (class "Default")
      (node (ref "IC4") (pin "12") (pinfunction "MOSI_12") (pintype "bidirectional"))
      (node (ref "IC5") (pin "5") (pinfunction "MOSI_5") (pintype "bidirectional"))
      (node (ref "R31") (pin "1") (pinfunction "1_1") (pintype "passive"))
    )
    (net (code "16") (name "/CC_FLASH_~{CS}") (class "Default")
      (node (ref "IC4") (pin "14") (pinfunction "~{CS}_14") (pintype "bidirectional"))
      (node (ref "IC5") (pin "1") (pinfunction "CS_1") (pintype "bidirectional"))
      (node (ref "R40") (pin "2") (pinfunction "2_2") (pintype "passive"))
    )
    (net (code "17") (name "/D2") (class "Default")
      (node (ref "IC3") (pin "82") (pinfunction "PD1_82") (pintype "bidirectional"))
      (node (ref "U2") (pin "D2") (pinfunction "D2_D2") (pintype "bidirectional"))
    )
    (net (code "18") (name "/D4") (class "Default")
      (node (ref "IC3") (pin "85") (pinfunction "PD4_85") (pintype "bidirectional"))
      (node (ref "U2") (pin "D4") (pinfunction "D4_D4") (pintype "bidirectional"))
    )
    (net (code "19") (name "/D7") (class "Default")
      (node (ref "IC3") (pin "81") (pinfunction "PD0_81") (pintype "bidirectional"))
      (node (ref "U2") (pin "D7") (pinfunction "D7_D7") (pintype "bidirectional"))
    )
    (net (code "20") (name "/D8") (class "Default")
      (node (ref "IC3") (pin "97") (pinfunction "PE0_97") (pintype "bidirectional"))
      (node (ref "JP4") (pin "1") (pinfunction "1_1") (pintype "passive"))
      (node (ref "U2") (pin "D8") (pinfunction "D8_D8") (pintype "bidirectional"))
    )
    (net (code "21") (name "/D_N") (class "Default")
      (node (ref "IC3") (pin "70") (pinfunction "PA11_70") (pintype "bidirectional"))
      (node (ref "R23") (pin "1") (pinfunction "1_1") (pintype "passive"))
    )
    (net (code "22") (name "/D_P") (class "Default")
      (node (ref "IC3") (pin "71") (pinfunction "PA12_71") (pintype "bidirectional"))
      (node (ref "R25") (pin "1") (pinfunction "1_1") (pintype "passive"))
    )
    (net (code "23") (name "/ESP_CH_PD") (class "Default")
      (node (ref "IC3") (pin "15") (pinfunction "PC0_15") (pintype "bidirectional"))
      (node (ref "X1") (pin "3") (pinfunction "CH_PD_3") (pintype "input"))
    )
    (net (code "24") (name "/ESP_GPIO0") (class "Default")
      (node (ref "IC3") (pin "16") (pinfunction "PC1_16") (pintype "bidirectional"))
      (node (ref "X1") (pin "12") (pinfunction "GPIO0_12") (pintype "bidirectional"))
    )
    (net (code "25") (name "/ESP_GPIO16") (class "Default")
      (node (ref "IC3") (pin "17") (pinfunction "PC2_17") (pintype "bidirectional"))
      (node (ref "X1") (pin "4") (pinfunction "GPIO16_4") (pintype "bidirectional"))
    )
    (net (code "27") (name "/FS_VUSB") (class "Default")
      (node (ref "IC3") (pin "68") (pinfunction "PA9_68") (pintype "bidirectional"))
      (node (ref "R10") (pin "1") (pinfunction "1_1") (pintype "passive"))
    )
    (net (code "28") (name "/I2C_SCL") (class "Default")
      (node (ref "IC3") (pin "92") (pinfunction "PB6_92") (pintype "bidirectional"))
      (node (ref "JP4") (pin "10") (pinfunction "10_10") (pintype "passive"))
      (node (ref "U2") (pin "SCL") (pinfunction "SCL_SCL") (pintype "bidirectional"))
    )
    (net (code "29") (name "/I2C_SDA") (class "Default")
      (node (ref "IC3") (pin "93") (pinfunction "PB7_93") (pintype "bidirectional"))
      (node (ref "JP4") (pin "9") (pinfunction "9_9") (pintype "passive"))
      (node (ref "U2") (pin "SDA") (pinfunction "SDA_SDA") (pintype "bidirectional"))
    )
    (net (code "30") (name "/JOY_DWN") (class "Default")
      (node (ref "IC3") (pin "59") (pinfunction "PD12_59") (pintype "bidirectional"))
      (node (ref "SW1") (pin "D") (pinfunction "DOWN_D") (pintype "bidirectional"))
    )
    (net (code "31") (name "/JOY_LEFT") (class "Default")
      (node (ref "IC3") (pin "58") (pinfunction "PD11_58") (pintype "bidirectional"))
      (node (ref "SW1") (pin "B") (pinfunction "LEFT_B") (pintype "bidirectional"))
    )
    (net (code "32") (name "/JOY_RIGHT") (class "Default")
      (node (ref "IC3") (pin "55") (pinfunction "PD8_55") (pintype "bidirectional"))
      (node (ref "SW1") (pin "C") (pinfunction "RIGHT_C") (pintype "bidirectional"))
    )
    (net (code "33") (name "/JOY_UP") (class "Default")
      (node (ref "IC3") (pin "57") (pinfunction "PD10_57") (pintype "bidirectional"))
      (node (ref "SW1") (pin "A") (pinfunction "UP_A") (pintype "bidirectional"))
    )
    (net (code "34") (name "/LCD_A0") (class "Default")
      (node (ref "IC3") (pin "88") (pinfunction "PD7_88") (pintype "bidirectional"))
      (node (ref "J2") (pin "4") (pinfunction "A0_4") (pintype "bidirectional"))
    )
    (net (code "35") (name "/LCD_P1+") (class "Default")
      (node (ref "C57") (pin "2") (pinfunction "2_2") (pintype "passive"))
      (node (ref "J2") (pin "20") (pinfunction "P1+_20") (pintype "bidirectional"))
    )
    (net (code "36") (name "/LCD_P1-") (class "Default")
      (node (ref "C57") (pin "1") (pinfunction "1_1") (pintype "passive"))
      (node (ref "C58") (pin "1") (pinfunction "1_1") (pintype "passive"))
      (node (ref "J2") (pin "19") (pinfunction "P1-_19") (pintype "bidirectional"))
    )
    (net (code "37") (name "/LCD_P2+") (class "Default")
      (node (ref "C60") (pin "2") (pinfunction "2_2") (pintype "passive"))
      (node (ref "J2") (pin "21") (pinfunction "P2+_21") (pintype "bidirectional"))
    )
    (net (code "38") (name "/LCD_P2-") (class "Default")
      (node (ref "C60") (pin "1") (pinfunction "1_1") (pintype "passive"))
      (node (ref "J2") (pin "22") (pinfunction "P2-_22") (pintype "bidirectional"))
    )
    (net (code "39") (name "/LCD_P3+") (class "Default")
      (node (ref "C58") (pin "2") (pinfunction "2_2") (pintype "passive"))
      (node (ref "J2") (pin "18") (pinfunction "P3+_18") (pintype "bidirectional"))
    )
    (net (code "40") (name "/LCD_POWER") (class "Default")
      (node (ref "IC3") (pin "90") (pinfunction "PB4_90") (pintype "bidirectional"))
      (node (ref "Q4") (pin "1") (pinfunction "G_1") (pintype "bidirectional"))
    )
    (net (code "41") (name "/LCD_V0") (class "Default")
      (node (ref "C51") (pin "2") (pinfunction "2_2") (pintype "passive"))
      (node (ref "J2") (pin "27") (pinfunction "V0_27") (pintype "bidirectional"))
    )
    (net (code "42") (name "/LCD_V1") (class "Default")
      (node (ref "C52") (pin "2") (pinfunction "2_2") (pintype "passive"))
      (node (ref "J2") (pin "26") (pinfunction "V1_26") (pintype "bidirectional"))
    )
    (net (code "43") (name "/LCD_V2") (class "Default")
      (node (ref "C63") (pin "2") (pinfunction "2_2") (pintype "passive"))
      (node (ref "J2") (pin "25") (pinfunction "V2_25") (pintype "bidirectional"))
    )
    (net (code "44") (name "/LCD_V3") (class "Default")
      (node (ref "C53") (pin "2") (pinfunction "2_2") (pintype "passive"))
      (node (ref "J2") (pin "24") (pinfunction "V3_24") (pintype "bidirectional"))
    )
    (net (code "45") (name "/LCD_V4") (class "Default")
      (node (ref "C54") (pin "2") (pinfunction "2_2") (pintype "passive"))
      (node (ref "J2") (pin "23") (pinfunction "V4_23") (pintype "bidirectional"))
    )
    (net (code "46") (name "/LCD_VCC") (class "Default")
      (node (ref "J2") (pin "10") (pinfunction "D3_10") (pintype "bidirectional"))
      (node (ref "J2") (pin "11") (pinfunction "D4_11") (pintype "bidirectional"))
      (node (ref "J2") (pin "12") (pinfunction "D5_12") (pintype "bidirectional"))
      (node (ref "J2") (pin "15") (pinfunction "VDD_15") (pintype "bidirectional"))
      (node (ref "J2") (pin "28") (pinfunction "C86_28") (pintype "bidirectional"))
      (node (ref "J2") (pin "5") (pinfunction "WR_5") (pintype "bidirectional"))
      (node (ref "J2") (pin "6") (pinfunction "RD_6") (pintype "bidirectional"))
      (node (ref "J2") (pin "7") (pinfunction "D0_7") (pintype "bidirectional"))
      (node (ref "J2") (pin "8") (pinfunction "D1_8") (pintype "bidirectional"))
      (node (ref "J2") (pin "9") (pinfunction "D2_9") (pintype "bidirectional"))
      (node (ref "Q4") (pin "3") (pinfunction "D_3") (pintype "bidirectional"))
    )
    (net (code "47") (name "/LCD_VOUT") (class "Default")
      (node (ref "C59") (pin "2") (pinfunction "2_2") (pintype "passive"))
      (node (ref "J2") (pin "17") (pinfunction "VOUT_17") (pintype "bidirectional"))
    )
    (net (code "48") (name "/LCD_~{RST}") (class "Default")
      (node (ref "IC3") (pin "98") (pinfunction "PE1_98") (pintype "bidirectional"))
      (node (ref "J2") (pin "3") (pinfunction "RST_3") (pintype "bidirectional"))
    )
    (net (code "49") (name "/LED1") (class "Default")
      (node (ref "IC3") (pin "46") (pinfunction "PE15_46") (pintype "bidirectional"))
      (node (ref "R12") (pin "2") (pinfunction "2_2") (pintype "passive"))
    )
    (net (code "50") (name "/LED2") (class "Default")
      (node (ref "IC3") (pin "47") (pinfunction "PB10_47") (pintype "bidirectional"))
      (node (ref "R14") (pin "2") (pinfunction "2_2") (pintype "passive"))
    )
    (net (code "51") (name "/MCO1") (class "Default")
      (node (ref "IC3") (pin "67") (pinfunction "PA8_67") (pintype "bidirectional"))
      (node (ref "R24") (pin "1") (pinfunction "1_1") (pintype "passive"))
    )
    (net (code "52") (name "/MOM_DWN") (class "Default")
      (node (ref "IC3") (pin "41") (pinfunction "PE10_41") (pintype "bidirectional"))
      (node (ref "S4") (pin "B2") (pinfunction "2_B2") (pintype "passive"))
    )
    (net (code "53") (name "/MOM_LEFT") (class "Default")
      (node (ref "IC3") (pin "37") (pinfunction "PB2_37") (pintype "bidirectional"))
      (node (ref "R11") (pin "2") (pinfunction "2_2") (pintype "passive"))
      (node (ref "S2") (pin "B2") (pinfunction "2_B2") (pintype "passive"))
    )
    (net (code "54") (name "/MOM_RIGHT") (class "Default")
      (node (ref "IC3") (pin "38") (pinfunction "PE7_38") (pintype "bidirectional"))
      (node (ref "S3") (pin "B2") (pinfunction "2_B2") (pintype "passive"))
    )
    (net (code "55") (name "/MOM_UP") (class "Default")
      (node (ref "IC3") (pin "3") (pinfunction "PE4_3") (pintype "bidirectional"))
      (node (ref "S1") (pin "A2") (pinfunction "1_A2") (pintype "passive"))
    )
    (net (code "56") (name "/NRST") (class "Default")
      (node (ref "IC3") (pin "14") (pinfunction "~{NRST}_14") (pintype "bidirectional"))
      (node (ref "J3") (pin "10") (pinfunction "NRST_10") (pintype "bidirectional"))
      (node (ref "U2") (pin "RESET") (pinfunction "/RESET_RESET") (pintype "bidirectional"))
    )
    (net (code "57") (name "/OCS32_IN") (class "Default")
      (node (ref "C23") (pin "2") (pinfunction "2_2") (pintype "passive"))
      (node (ref "IC3") (pin "8") (pinfunction "PC14/OSC32_IN_8") (pintype "bidirectional"))
      (node (ref "X3") (pin "P$1") (pinfunction "1_P$1") (pintype "bidirectional"))
    )
    (net (code "58") (name "/OCS32_OUT") (class "Default")
      (node (ref "C24") (pin "2") (pinfunction "2_2") (pintype "passive"))
      (node (ref "IC3") (pin "9") (pinfunction "PC15/OSC32_OUT_9") (pintype "bidirectional"))
      (node (ref "X3") (pin "P$2") (pinfunction "2_P$2") (pintype "bidirectional"))
    )
    (net (code "59") (name "/SDIO_CLK") (class "Default")
      (node (ref "IC3") (pin "80") (pinfunction "PC12_80") (pintype "bidirectional"))
      (node (ref "U4") (pin "5") (pinfunction "SCK_5") (pintype "bidirectional"))
    )
    (net (code "60") (name "/SDIO_CMD") (class "Default")
      (node (ref "IC3") (pin "83") (pinfunction "PD2_83") (pintype "bidirectional"))
      (node (ref "U4") (pin "3") (pinfunction "DI_3") (pintype "bidirectional"))
    )
    (net (code "61") (name "/SDIO_D0") (class "Default")
      (node (ref "IC3") (pin "65") (pinfunction "PC8_65") (pintype "bidirectional"))
      (node (ref "U4") (pin "7") (pinfunction "DO_7") (pintype "bidirectional"))
    )
    (net (code "62") (name "/SDIO_D1") (class "Default")
      (node (ref "IC3") (pin "66") (pinfunction "PC9_66") (pintype "bidirectional"))
      (node (ref "U4") (pin "8") (pinfunction "RSV_8") (pintype "bidirectional"))
    )
    (net (code "63") (name "/SDIO_D2") (class "Default")
      (node (ref "IC3") (pin "78") (pinfunction "PC10_78") (pintype "bidirectional"))
      (node (ref "U4") (pin "1") (pinfunction "NC_1") (pintype "bidirectional"))
    )
    (net (code "64") (name "/SDIO_D3") (class "Default")
      (node (ref "IC3") (pin "79") (pinfunction "PC11_79") (pintype "bidirectional"))
      (node (ref "U4") (pin "2") (pinfunction "CS_2") (pintype "bidirectional"))
    )
    (net (code "65") (name "/SDIO_SW") (class "Default")
      (node (ref "IC3") (pin "62") (pinfunction "PD15_62") (pintype "bidirectional"))
      (node (ref "U4") (pin "CD1") (pinfunction "SHIELD_CD1") (pintype "bidirectional"))
    )
    (net (code "66") (name "/SPI1_MISO") (class "Default")
      (node (ref "IC3") (pin "31") (pinfunction "PA6_31") (pintype "bidirectional"))
      (node (ref "IC4") (pin "7") (pinfunction "MISO_7") (pintype "bidirectional"))
    )
    (net (code "67") (name "/SPI1_MOSI") (class "Default")
      (node (ref "IC3") (pin "32") (pinfunction "PA7_32") (pintype "bidirectional"))
      (node (ref "IC4") (pin "6") (pinfunction "MOSI_6") (pintype "bidirectional"))
    )
    (net (code "68") (name "/SPI1_NSS") (class "Default")
      (node (ref "IC3") (pin "29") (pinfunction "PA4_29") (pintype "bidirectional"))
      (node (ref "IC4") (pin "8") (pinfunction "~{CS}_8") (pintype "bidirectional"))
    )
    (net (code "69") (name "/SPI1_SCK") (class "Default")
      (node (ref "IC3") (pin "30") (pinfunction "PA5_30") (pintype "bidirectional"))
      (node (ref "IC4") (pin "5") (pinfunction "CLK_5") (pintype "bidirectional"))
    )
    (net (code "70") (name "/SPI2_CLK") (class "Default")
      (node (ref "IC3") (pin "84") (pinfunction "PD3_84") (pintype "bidirectional"))
      (node (ref "JP4") (pin "6") (pinfunction "6_6") (pintype "passive"))
      (node (ref "U2") (pin "D13") (pinfunction "D13_D13") (pintype "bidirectional"))
    )
    (net (code "71") (name "/SPI2_MISO") (class "Default")
      (node (ref "IC3") (pin "53") (pinfunction "PB14_53") (pintype "bidirectional"))
      (node (ref "JP4") (pin "5") (pinfunction "5_5") (pintype "passive"))
      (node (ref "U2") (pin "D12") (pinfunction "D12_D12") (pintype "bidirectional"))
    )
    (net (code "72") (name "/SPI2_MOSI") (class "Default")
      (node (ref "IC3") (pin "54") (pinfunction "PB15_54") (pintype "bidirectional"))
      (node (ref "JP4") (pin "4") (pinfunction "4_4") (pintype "passive"))
      (node (ref "U2") (pin "D11") (pinfunction "D11_D11") (pintype "bidirectional"))
    )
    (net (code "73") (name "/SPI3_MOSI") (class "Default")
      (node (ref "IC3") (pin "91") (pinfunction "PB5_91") (pintype "bidirectional"))
      (node (ref "J2") (pin "14") (pinfunction "D7_14") (pintype "bidirectional"))
    )
    (net (code "74") (name "/SPI3_NSS") (class "Default")
      (node (ref "IC3") (pin "77") (pinfunction "PA15_77") (pintype "bidirectional"))
      (node (ref "J2") (pin "2") (pinfunction "CS1B_2") (pintype "bidirectional"))
    )
    (net (code "75") (name "/SPI3_SCK") (class "Default")
      (node (ref "IC3") (pin "89") (pinfunction "PB3_89") (pintype "bidirectional"))
      (node (ref "J2") (pin "13") (pinfunction "D6_13") (pintype "bidirectional"))
    )
    (net (code "76") (name "/SPI4_MOSI") (class "Default")
      (node (ref "D1") (pin "4") (pinfunction "DIN_4") (pintype "input"))
      (node (ref "IC3") (pin "5") (pinfunction "PE6_5") (pintype "bidirectional"))
    )
    (net (code "77") (name "/SWCLK") (class "Default")
      (node (ref "IC3") (pin "76") (pinfunction "PA14_76") (pintype "bidirectional"))
      (node (ref "J3") (pin "4") (pinfunction "SWCLK_4") (pintype "bidirectional"))
    )
    (net (code "78") (name "/SWDAT") (class "Default")
      (node (ref "IC3") (pin "72") (pinfunction "PA13_72") (pintype "bidirectional"))
      (node (ref "J3") (pin "2") (pinfunction "SWDAT_2") (pintype "bidirectional"))
    )
    (net (code "79") (name "/TIM1_CH1") (class "Default")
      (node (ref "IC3") (pin "40") (pinfunction "PE9_40") (pintype "bidirectional"))
      (node (ref "SV3") (pin "3") (pinfunction "3_3") (pintype "passive"))
      (node (ref "TP3") (pin "P$1") (pinfunction "TP_P$1") (pintype "input"))
    )
    (net (code "80") (name "/TIM1_CH1N") (class "Default")
      (node (ref "IC3") (pin "52") (pinfunction "PB13_52") (pintype "bidirectional"))
      (node (ref "Q5") (pin "1") (pinfunction "G_1") (pintype "bidirectional"))
      (node (ref "U2") (pin "D3") (pinfunction "D3_D3") (pintype "bidirectional"))
    )
    (net (code "81") (name "/TIM1_CH2") (class "Default")
      (node (ref "IC3") (pin "42") (pinfunction "PE11_42") (pintype "bidirectional"))
      (node (ref "SV5") (pin "3") (pinfunction "3_3") (pintype "passive"))
      (node (ref "TP4") (pin "P$1") (pinfunction "TP_P$1") (pintype "input"))
    )
    (net (code "82") (name "/TIM1_CH3") (class "Default")
      (node (ref "IC3") (pin "44") (pinfunction "PE13_44") (pintype "bidirectional"))
      (node (ref "SV6") (pin "3") (pinfunction "3_3") (pintype "passive"))
      (node (ref "TP10") (pin "P$1") (pinfunction "TP_P$1") (pintype "input"))
    )
    (net (code "83") (name "/TIM1_CH4") (class "Default")
      (node (ref "IC3") (pin "45") (pinfunction "PE14_45") (pintype "bidirectional"))
      (node (ref "SV4") (pin "3") (pinfunction "3_3") (pintype "passive"))
      (node (ref "TP9") (pin "P$1") (pinfunction "TP_P$1") (pintype "input"))
    )
    (net (code "84") (name "/TIM4_CH2") (class "Default")
      (node (ref "IC3") (pin "60") (pinfunction "PD13_60") (pintype "bidirectional"))
      (node (ref "U2") (pin "D5") (pinfunction "D5_D5") (pintype "bidirectional"))
    )
    (net (code "85") (name "/TIM4_CH3") (class "Default")
      (node (ref "IC3") (pin "61") (pinfunction "PD14_61") (pintype "bidirectional"))
      (node (ref "U2") (pin "D6") (pinfunction "D6_D6") (pintype "bidirectional"))
    )
    (net (code "86") (name "/TIM9_CH1") (class "Default")
      (node (ref "IC3") (pin "4") (pinfunction "PE5_4") (pintype "bidirectional"))
      (node (ref "Q3") (pin "1") (pinfunction "G_1") (pintype "bidirectional"))
    )
    (net (code "87") (name "/TIM10_CH1") (class "Default")
      (node (ref "IC3") (pin "95") (pinfunction "PB8_95") (pintype "bidirectional"))
      (node (ref "JP4") (pin "2") (pinfunction "2_2") (pintype "passive"))
      (node (ref "U2") (pin "D9") (pinfunction "D9_D9") (pintype "bidirectional"))
    )
    (net (code "88") (name "/TIM11_CH1") (class "Default")
      (node (ref "IC3") (pin "96") (pinfunction "PB9_96") (pintype "bidirectional"))
      (node (ref "JP4") (pin "3") (pinfunction "3_3") (pintype "passive"))
      (node (ref "U2") (pin "D10") (pinfunction "D10_D10") (pintype "bidirectional"))
    )
    (net (code "89") (name "/USART2_RX") (class "Default")
      (node (ref "IC3") (pin "87") (pinfunction "PD6_87") (pintype "bidirectional"))
      (node (ref "TP1") (pin "P$1") (pinfunction "TP_P$1") (pintype "input"))
      (node (ref "U2") (pin "D0") (pinfunction "D0_D0") (pintype "bidirectional"))
    )
    (net (code "90") (name "/USART2_TX") (class "Default")
      (node (ref "IC3") (pin "86") (pinfunction "PD5_86") (pintype "bidirectional"))
      (node (ref "TP2") (pin "P$1") (pinfunction "TP_P$1") (pintype "input"))
      (node (ref "U2") (pin "D1") (pinfunction "D1_D1") (pintype "bidirectional"))
    )
    (net (code "91") (name "/USART6_RX") (class "Default")
      (node (ref "IC3") (pin "64") (pinfunction "PC7_64") (pintype "bidirectional"))
      (node (ref "R46") (pin "1") (pinfunction "1_1") (pintype "passive"))
      (node (ref "X1") (pin "16") (pinfunction "UTXD_16") (pintype "output"))
    )
    (net (code "92") (name "/USART6_TX") (class "Default")
      (node (ref "IC3") (pin "63") (pinfunction "PC6_63") (pintype "bidirectional"))
      (node (ref "IC4") (pin "57") (pinfunction "RX_57") (pintype "bidirectional"))
      (node (ref "SV1") (pin "2") (pinfunction "2_2") (pintype "passive"))
      (node (ref "X1") (pin "15") (pinfunction "URXD_15") (pintype "input"))
    )
    (net (code "93") (name "/USB_ID") (class "Default")
      (node (ref "J1") (pin "ID") (pinfunction "USBID_ID") (pintype "bidirectional"))
      (node (ref "SJ3") (pin "2") (pinfunction "2_2") (pintype "passive"))
      (node (ref "Z1") (pin "1") (pinfunction "1_1") (pintype "passive"))
    )
    (net (code "94") (name "/USB_ID_") (class "Default")
      (node (ref "IC3") (pin "69") (pinfunction "PA10_69") (pintype "bidirectional"))
      (node (ref "SJ3") (pin "1") (pinfunction "1_1") (pintype "passive"))
    )
    (net (code "95") (name "/VBATT_IN") (class "Default")
      (node (ref "C33") (pin "2") (pinfunction "2_2") (pintype "passive"))
      (node (ref "IC3") (pin "6") (pinfunction "VBAT_6") (pintype "bidirectional"))
      (node (ref "R21") (pin "1") (pinfunction "1_1") (pintype "passive"))
      (node (ref "R22") (pin "1") (pinfunction "1_1") (pintype "passive"))
    )
    (net (code "96") (name "/VBUS") (class "Default")
      (node (ref "C1") (pin "2") (pinfunction "2_2") (pintype "passive"))
      (node (ref "C4") (pin "+") (pinfunction "+_+") (pintype "passive"))
      (node (ref "D3") (pin "A") (pinfunction "A_A") (pintype "passive"))
      (node (ref "L2") (pin "2") (pinfunction "2_2") (pintype "passive"))
      (node (ref "R10") (pin "2") (pinfunction "2_2") (pintype "passive"))
      (node (ref "R18") (pin "1") (pinfunction "1_1") (pintype "passive"))
      (node (ref "R2") (pin "2") (pinfunction "2_2") (pintype "passive"))
      (node (ref "SJ1") (pin "2") (pinfunction "2_2") (pintype "passive"))
      (node (ref "U2") (pin "5V") (pinfunction "5V_5V") (pintype "power_in"))
      (node (ref "U2") (pin "VIN") (pinfunction "VIN_VIN") (pintype "power_in"))
      (node (ref "U3") (pin "4") (pinfunction "VIN_4") (pintype "power_in"))
    )
    (net (code "97") (name "/V_UNREG") (class "Default")
      (node (ref "C6") (pin "1") (pinfunction "1_1") (pintype "passive"))
      (node (ref "D2") (pin "A") (pinfunction "A_A") (pintype "passive"))
      (node (ref "IC2") (pin "3") (pinfunction "VIN_3") (pintype "power_in"))
      (node (ref "Q6") (pin "3") (pinfunction "D_3") (pintype "bidirectional"))
      (node (ref "R3") (pin "1") (pinfunction "1_1") (pintype "passive"))
      (node (ref "R7") (pin "1") (pinfunction "1_1") (pintype "passive"))
      (node (ref "SV2") (pin "2") (pinfunction "2_2") (pintype "passive"))
      (node (ref "SV3") (pin "2") (pinfunction "2_2") (pintype "passive"))
      (node (ref "SV4") (pin "2") (pinfunction "2_2") (pintype "passive"))
      (node (ref "SV5") (pin "2") (pinfunction "2_2") (pintype "passive"))
      (node (ref "SV6") (pin "2") (pinfunction "2_2") (pintype "passive"))
    )
    (net (code "98") (name "/WIFI_FORCE_AP") (class "Default")
      (node (ref "IC4") (pin "4") (pinfunction "FORCE_AP_4") (pintype "bidirectional"))
      (node (ref "R28") (pin "1") (pinfunction "1_1") (pintype "passive"))
    )
    (net (code "99") (name "/WIFI_INTR") (class "Default")
      (node (ref "IC3") (pin "2") (pinfunction "PE3_2") (pintype "bidirectional"))
      (node (ref "IC4") (pin "15") (pinfunction "HOST_INTR_15") (pintype "bidirectional"))
    )
    (net (code "100") (name "/WIFI_SOP0") (class "Default")
      (node (ref "IC4") (pin "35") (pinfunction "SOP0_35") (pintype "bidirectional"))
      (node (ref "R35") (pin "1") (pinfunction "1_1") (pintype "passive"))
    )
    (net (code "101") (name "/WIFI_SOP1") (class "Default")
      (node (ref "IC4") (pin "34") (pinfunction "SOP1_34") (pintype "bidirectional"))
      (node (ref "R36") (pin "1") (pinfunction "1_1") (pintype "passive"))
    )
    (net (code "102") (name "/WIFI_SOP2") (class "Default")
      (node (ref "IC4") (pin "21") (pinfunction "SOP2/TCXO_EN_21") (pintype "bidirectional"))
      (node (ref "R37") (pin "1") (pinfunction "1_1") (pintype "passive"))
    )
    (net (code "103") (name "/WIFI_~{HIB}") (class "Default")
      (node (ref "IC3") (pin "7") (pinfunction "PC13_7") (pintype "bidirectional"))
      (node (ref "IC4") (pin "2") (pinfunction "~{HIB}_2") (pintype "bidirectional"))
    )
    (net (code "104") (name "/WIFI_~{RESET}") (class "Default")
      (node (ref "C64") (pin "2") (pinfunction "2_2") (pintype "passive"))
      (node (ref "IC3") (pin "39") (pinfunction "PE8_39") (pintype "bidirectional"))
      (node (ref "IC4") (pin "32") (pinfunction "~{RESET}_32") (pintype "bidirectional"))
      (node (ref "R38") (pin "2") (pinfunction "2_2") (pintype "passive"))
      (node (ref "S6") (pin "1") (pinfunction "1_1") (pintype "passive"))
    )
    (net (code "105") (name "GND") (class "Default")
      (node (ref "C1") (pin "1") (pinfunction "1_1") (pintype "passive"))
      (node (ref "C10") (pin "1") (pinfunction "1_1") (pintype "passive"))
      (node (ref "C11") (pin "1") (pinfunction "1_1") (pintype "passive"))
      (node (ref "C12") (pin "1") (pinfunction "1_1") (pintype "passive"))
      (node (ref "C13") (pin "1") (pinfunction "1_1") (pintype "passive"))
      (node (ref "C14") (pin "1") (pinfunction "1_1") (pintype "passive"))
      (node (ref "C15") (pin "1") (pinfunction "1_1") (pintype "passive"))
      (node (ref "C16") (pin "1") (pinfunction "1_1") (pintype "passive"))
      (node (ref "C17") (pin "1") (pinfunction "1_1") (pintype "passive"))
      (node (ref "C18") (pin "1") (pinfunction "1_1") (pintype "passive"))
      (node (ref "C19") (pin "1") (pinfunction "1_1") (pintype "passive"))
      (node (ref "C2") (pin "2") (pinfunction "2_2") (pintype "passive"))
      (node (ref "C20") (pin "1") (pinfunction "1_1") (pintype "passive"))
      (node (ref "C21") (pin "1") (pinfunction "1_1") (pintype "passive"))
      (node (ref "C22") (pin "1") (pinfunction "1_1") (pintype "passive"))
      (node (ref "C23") (pin "1") (pinfunction "1_1") (pintype "passive"))
      (node (ref "C24") (pin "1") (pinfunction "1_1") (pintype "passive"))
      (node (ref "C25") (pin "1") (pinfunction "1_1") (pintype "passive"))
      (node (ref "C26") (pin "1") (pinfunction "1_1") (pintype "passive"))
      (node (ref "C27") (pin "1") (pinfunction "1_1") (pintype "passive"))
      (node (ref "C28") (pin "1") (pinfunction "1_1") (pintype "passive"))
      (node (ref "C29") (pin "1") (pinfunction "1_1") (pintype "passive"))
      (node (ref "C3") (pin "1") (pinfunction "1_1") (pintype "passive"))
      (node (ref "C30") (pin "1") (pinfunction "1_1") (pintype "passive"))
      (node (ref "C31") (pin "1") (pinfunction "1_1") (pintype "passive"))
      (node (ref "C32") (pin "1") (pinfunction "1_1") (pintype "passive"))
      (node (ref "C33") (pin "1") (pinfunction "1_1") (pintype "passive"))
      (node (ref "C34") (pin "1") (pinfunction "1_1") (pintype "passive"))
      (node (ref "C35") (pin "1") (pinfunction "1_1") (pintype "passive"))
      (node (ref "C36") (pin "1") (pinfunction "1_1") (pintype "passive"))
      (node (ref "C37") (pin "1") (pinfunction "1_1") (pintype "passive"))
      (node (ref "C39") (pin "1") (pinfunction "1_1") (pintype "passive"))
      (node (ref "C4") (pin "-") (pinfunction "-_-") (pintype "passive"))
      (node (ref "C40") (pin "1") (pinfunction "1_1") (pintype "passive"))
      (node (ref "C41") (pin "1") (pinfunction "1_1") (pintype "passive"))
      (node (ref "C42") (pin "1") (pinfunction "1_1") (pintype "passive"))
      (node (ref "C43") (pin "1") (pinfunction "1_1") (pintype "passive"))
      (node (ref "C44") (pin "1") (pinfunction "1_1") (pintype "passive"))
      (node (ref "C46") (pin "1") (pinfunction "1_1") (pintype "passive"))
      (node (ref "C47") (pin "1") (pinfunction "1_1") (pintype "passive"))
      (node (ref "C49") (pin "1") (pinfunction "1_1") (pintype "passive"))
      (node (ref "C5") (pin "2") (pinfunction "2_2") (pintype "passive"))
      (node (ref "C50") (pin "1") (pinfunction "1_1") (pintype "passive"))
      (node (ref "C51") (pin "1") (pinfunction "1_1") (pintype "passive"))
      (node (ref "C52") (pin "1") (pinfunction "1_1") (pintype "passive"))
      (node (ref "C53") (pin "1") (pinfunction "1_1") (pintype "passive"))
      (node (ref "C54") (pin "1") (pinfunction "1_1") (pintype "passive"))
      (node (ref "C55") (pin "1") (pinfunction "1_1") (pintype "passive"))
      (node (ref "C56") (pin "1") (pinfunction "1_1") (pintype "passive"))
      (node (ref "C59") (pin "1") (pinfunction "1_1") (pintype "passive"))
      (node (ref "C6") (pin "2") (pinfunction "2_2") (pintype "passive"))
      (node (ref "C62") (pin "1") (pinfunction "1_1") (pintype "passive"))
      (node (ref "C63") (pin "1") (pinfunction "1_1") (pintype "passive"))
      (node (ref "C64") (pin "1") (pinfunction "1_1") (pintype "passive"))
      (node (ref "C65") (pin "1") (pinfunction "1_1") (pintype "passive"))
      (node (ref "C67") (pin "2") (pinfunction "2_2") (pintype "passive"))
      (node (ref "C68") (pin "1") (pinfunction "1_1") (pintype "passive"))
      (node (ref "C69") (pin "1") (pinfunction "1_1") (pintype "passive"))
      (node (ref "C7") (pin "2") (pinfunction "2_2") (pintype "passive"))
      (node (ref "C70") (pin "2") (pinfunction "2_2") (pintype "passive"))
      (node (ref "C8") (pin "1") (pinfunction "1_1") (pintype "passive"))
      (node (ref "C9") (pin "1") (pinfunction "1_1") (pintype "passive"))
      (node (ref "D1") (pin "3") (pinfunction "VSS_3") (pintype "power_in"))
      (node (ref "FL1") (pin "GND@2") (pinfunction "GND_GND@2") (pintype "bidirectional"))
      (node (ref "FL1") (pin "GND@4") (pinfunction "GND_GND@4") (pintype "bidirectional"))
      (node (ref "G1") (pin "P$3") (pinfunction "1_P$3") (pintype "passive"))
      (node (ref "G1") (pin "P$4") (pinfunction "2_P$4") (pintype "passive"))
      (node (ref "IC1") (pin "3") (pinfunction "GND_3") (pintype "power_in"))
      (node (ref "IC2") (pin "2") (pinfunction "GND_2") (pintype "power_in"))
      (node (ref "IC2") (pin "4") (pinfunction "GND_4") (pintype "power_in"))
      (node (ref "IC2") (pin "EP") (pinfunction "GND_EP") (pintype "power_in"))
      (node (ref "IC3") (pin "10") (pinfunction "VSS1_10") (pintype "bidirectional"))
      (node (ref "IC3") (pin "20") (pinfunction "VSSA/VREF-_20") (pintype "bidirectional"))
      (node (ref "IC3") (pin "27") (pinfunction "VSS2_27") (pintype "bidirectional"))
      (node (ref "IC3") (pin "74") (pinfunction "VSS3_74") (pintype "bidirectional"))
      (node (ref "IC3") (pin "99") (pinfunction "VSS4_99") (pintype "bidirectional"))
      (node (ref "IC4") (pin "PAD") (pinfunction "GND_PAD") (pintype "bidirectional"))
      (node (ref "IC5") (pin "4") (pinfunction "GND_4") (pintype "bidirectional"))
      (node (ref "J1") (pin "GND") (pinfunction "GND_GND") (pintype "bidirectional"))
      (node (ref "J1") (pin "SHIELD") (pinfunction "SHIELD_SHIELD") (pintype "bidirectional"))
      (node (ref "J1") (pin "SHIELD@0") (pinfunction "SHIELD_SHIELD@0") (pintype "bidirectional"))
      (node (ref "J1") (pin "SHIELD@1") (pinfunction "SHIELD_SHIELD@1") (pintype "bidirectional"))
      (node (ref "J1") (pin "SHIELD@2") (pinfunction "SHIELD_SHIELD@2") (pintype "bidirectional"))
      (node (ref "J1") (pin "SHIELD@3") (pinfunction "SHIELD_SHIELD@3") (pintype "bidirectional"))
      (node (ref "J1") (pin "SHIELD@5") (pinfunction "SHIELD_SHIELD@5") (pintype "bidirectional"))
      (node (ref "J2") (pin "16") (pinfunction "VSS_16") (pintype "bidirectional"))
      (node (ref "J2") (pin "29") (pinfunction "PS_29") (pintype "bidirectional"))
      (node (ref "J2") (pin "M1") (pinfunction "VSS_M1") (pintype "bidirectional"))
      (node (ref "J2") (pin "M2") (pinfunction "VSS_M2") (pintype "bidirectional"))
      (node (ref "J3") (pin "3") (pinfunction "GND1_3") (pintype "power_in"))
      (node (ref "J3") (pin "5") (pinfunction "GND2_5") (pintype "power_in"))
      (node (ref "J3") (pin "9") (pinfunction "GNDD_9") (pintype "power_in"))
      (node (ref "JP3") (pin "1") (pinfunction "1_1") (pintype "passive"))
      (node (ref "JP4") (pin "7") (pinfunction "7_7") (pintype "passive"))
      (node (ref "LED1") (pin "K") (pinfunction "C_K") (pintype "passive"))
      (node (ref "LED2") (pin "C") (pinfunction "C_C") (pintype "passive"))
      (node (ref "LED3") (pin "C") (pinfunction "C_C") (pintype "passive"))
      (node (ref "R11") (pin "1") (pinfunction "1_1") (pintype "passive"))
      (node (ref "R15") (pin "2") (pinfunction "2_2") (pintype "passive"))
      (node (ref "R16") (pin "2") (pinfunction "2_2") (pintype "passive"))
      (node (ref "R19") (pin "2") (pinfunction "2_2") (pintype "passive"))
      (node (ref "R22") (pin "2") (pinfunction "2_2") (pintype "passive"))
      (node (ref "R27") (pin "2") (pinfunction "2_2") (pintype "passive"))
      (node (ref "R28") (pin "2") (pinfunction "2_2") (pintype "passive"))
      (node (ref "R30") (pin "1") (pinfunction "1_1") (pintype "passive"))
      (node (ref "R31") (pin "2") (pinfunction "2_2") (pintype "passive"))
      (node (ref "R33") (pin "1") (pinfunction "1_1") (pintype "passive"))
      (node (ref "R34") (pin "2") (pinfunction "2_2") (pintype "passive"))
      (node (ref "R35") (pin "2") (pinfunction "2_2") (pintype "passive"))
      (node (ref "R36") (pin "2") (pinfunction "2_2") (pintype "passive"))
      (node (ref "R37") (pin "2") (pinfunction "2_2") (pintype "passive"))
      (node (ref "R39") (pin "2") (pinfunction "2_2") (pintype "passive"))
      (node (ref "R4") (pin "2") (pinfunction "2_2") (pintype "passive"))
      (node (ref "R5") (pin "2") (pinfunction "2_2") (pintype "passive"))
      (node (ref "R6") (pin "2") (pinfunction "2_2") (pintype "passive"))
      (node (ref "R9") (pin "2") (pinfunction "2_2") (pintype "passive"))
      (node (ref "S5") (pin "2") (pinfunction "P_2") (pintype "passive"))
      (node (ref "S6") (pin "2") (pinfunction "2_2") (pintype "passive"))
      (node (ref "SV1") (pin "1") (pinfunction "1_1") (pintype "passive"))
      (node (ref "SV2") (pin "1") (pinfunction "1_1") (pintype "passive"))
      (node (ref "SV3") (pin "1") (pinfunction "1_1") (pintype "passive"))
      (node (ref "SV4") (pin "1") (pinfunction "1_1") (pintype "passive"))
      (node (ref "SV5") (pin "1") (pinfunction "1_1") (pintype "passive"))
      (node (ref "SV6") (pin "1") (pinfunction "1_1") (pintype "passive"))
      (node (ref "TP5") (pin "P$1") (pinfunction "TP_P$1") (pintype "input"))
      (node (ref "U1") (pin "K") (pinfunction "K_K") (pintype "bidirectional"))
      (node (ref "U2") (pin "GND") (pinfunction "GND_GND") (pintype "power_in"))
      (node (ref "U2") (pin "GND1") (pinfunction "GND1_GND1") (pintype "power_in"))
      (node (ref "U2") (pin "GND2") (pinfunction "GND2_GND2") (pintype "power_in"))
      (node (ref "U3") (pin "2") (pinfunction "VSS_2") (pintype "power_in"))
      (node (ref "U4") (pin "6") (pinfunction "GND_6") (pintype "bidirectional"))
      (node (ref "U4") (pin "CD2") (pinfunction "SHIELD_CD2") (pintype "bidirectional"))
      (node (ref "U4") (pin "GND1") (pinfunction "SHIELD_GND1") (pintype "bidirectional"))
      (node (ref "U4") (pin "GND3") (pinfunction "SHIELD_GND3") (pintype "bidirectional"))
      (node (ref "X1") (pin "9") (pinfunction "GND_9") (pintype "power_in"))
      (node (ref "X2") (pin "2") (pinfunction "GND_2") (pintype "passive"))
      (node (ref "X2") (pin "4") (pinfunction "GND_4") (pintype "passive"))
      (node (ref "X5") (pin "2") (pinfunction "GND_2") (pintype "passive"))
      (node (ref "X5") (pin "4") (pinfunction "GND_4") (pintype "passive"))
      (node (ref "X6") (pin "2@1") (pinfunction "GND_2@1") (pintype "passive"))
      (node (ref "X6") (pin "2@2") (pinfunction "GND_2@2") (pintype "passive"))
      (node (ref "Z1") (pin "2") (pinfunction "2_2") (pintype "passive"))
      (node (ref "Z2") (pin "2") (pinfunction "2_2") (pintype "passive"))
      (node (ref "Z3") (pin "2") (pinfunction "2_2") (pintype "passive"))
    )
    (net (code "106") (name "Net-(ANT2-1)") (class "Default")
      (node (ref "ANT2") (pin "P$1") (pinfunction "1_P$1") (pintype "passive"))
      (node (ref "C70") (pin "1") (pinfunction "1_1") (pintype "passive"))
      (node (ref "L7") (pin "2") (pinfunction "2_2") (pintype "passive"))
    )
    (net (code "107") (name "Net-(C67-Pad1)") (class "Default")
      (node (ref "C67") (pin "1") (pinfunction "1_1") (pintype "passive"))
      (node (ref "FL1") (pin "OUT") (pinfunction "OUT_OUT") (pintype "bidirectional"))
      (node (ref "L7") (pin "1") (pinfunction "1_1") (pintype "passive"))
      (node (ref "R41") (pin "2") (pinfunction "2_2") (pintype "passive"))
    )
    (net (code "108") (name "Net-(D1-DOUT)") (class "Default")
      (node (ref "D1") (pin "2") (pinfunction "DOUT_2") (pintype "output"))
      (node (ref "SV2") (pin "3") (pinfunction "3_3") (pintype "passive"))
    )
    (net (code "109") (name "Net-(D2-PadC)") (class "Default")
      (node (ref "D2") (pin "C") (pinfunction "C_C") (pintype "passive"))
      (node (ref "SJ1") (pin "1") (pinfunction "1_1") (pintype "passive"))
    )
    (net (code "110") (name "Net-(IC1-OUT)") (class "Default")
      (node (ref "C7") (pin "1") (pinfunction "1_1") (pintype "passive"))
      (node (ref "IC1") (pin "1") (pinfunction "OUT_1") (pintype "output"))
      (node (ref "IC2") (pin "6") (pinfunction "EN_6") (pintype "input"))
    )
    (net (code "111") (name "Net-(IC1-VDD)") (class "Default")
      (node (ref "C2") (pin "1") (pinfunction "1_1") (pintype "passive"))
      (node (ref "IC1") (pin "2") (pinfunction "VDD_2") (pintype "power_in"))
      (node (ref "R7") (pin "2") (pinfunction "2_2") (pintype "passive"))
    )
    (net (code "112") (name "Net-(IC2-FB)") (class "Default")
      (node (ref "IC2") (pin "1") (pinfunction "FB_1") (pintype "input"))
      (node (ref "R8") (pin "2") (pinfunction "2_2") (pintype "passive"))
      (node (ref "R9") (pin "1") (pinfunction "1_1") (pintype "passive"))
    )
    (net (code "113") (name "Net-(IC2-SW)") (class "Default")
      (node (ref "IC2") (pin "5") (pinfunction "SW_5") (pintype "bidirectional"))
      (node (ref "L1") (pin "1") (pinfunction "1_1") (pintype "passive"))
    )
    (net (code "114") (name "Net-(IC3F-PH0{slash}OCS_IN)") (class "Default")
      (node (ref "C21") (pin "2") (pinfunction "2_2") (pintype "passive"))
      (node (ref "IC3") (pin "12") (pinfunction "PH0/OCS_IN_12") (pintype "bidirectional"))
      (node (ref "X2") (pin "3") (pinfunction "C2_3") (pintype "passive"))
    )
    (net (code "115") (name "Net-(IC3F-PH1{slash}OSC_OUT)") (class "Default")
      (node (ref "IC3") (pin "13") (pinfunction "PH1/OSC_OUT_13") (pintype "bidirectional"))
      (node (ref "R43") (pin "1") (pinfunction "1_1") (pintype "passive"))
    )
    (net (code "116") (name "Net-(IC3G-VCAP1)") (class "Default")
      (node (ref "C9") (pin "2") (pinfunction "2_2") (pintype "passive"))
      (node (ref "IC3") (pin "48") (pinfunction "VCAP1_48") (pintype "bidirectional"))
    )
    (net (code "117") (name "Net-(IC3G-VCAP2)") (class "Default")
      (node (ref "C29") (pin "2") (pinfunction "2_2") (pintype "passive"))
      (node (ref "IC3") (pin "73") (pinfunction "VCAP2_73") (pintype "bidirectional"))
    )
    (net (code "118") (name "Net-(IC3G-VDDA)") (class "Default")
      (node (ref "C15") (pin "2") (pinfunction "2_2") (pintype "passive"))
      (node (ref "C16") (pin "2") (pinfunction "2_2") (pintype "passive"))
      (node (ref "IC3") (pin "21") (pinfunction "VREF+_21") (pintype "bidirectional"))
      (node (ref "IC3") (pin "22") (pinfunction "VDDA_22") (pintype "bidirectional"))
      (node (ref "L3") (pin "2") (pinfunction "2_2") (pintype "passive"))
    )
    (net (code "119") (name "Net-(IC3G-VSS)") (class "Default")
      (node (ref "C10") (pin "2") (pinfunction "2_2") (pintype "passive"))
      (node (ref "IC3") (pin "49") (pinfunction "VSS_49") (pintype "bidirectional"))
    )
    (net (code "120") (name "Net-(IC4A-RF_BG)") (class "Default")
      (node (ref "FL1") (pin "IN") (pinfunction "IN_IN") (pintype "bidirectional"))
      (node (ref "IC4") (pin "31") (pinfunction "RF_BG_31") (pintype "bidirectional"))
    )
    (net (code "121") (name "Net-(IC4B-RESERVED-Pad3)") (class "Default")
      (node (ref "IC4") (pin "3") (pinfunction "RESERVED_3") (pintype "bidirectional"))
      (node (ref "R27") (pin "1") (pinfunction "1_1") (pintype "passive"))
    )
    (net (code "122") (name "Net-(IC4B-RESERVED-Pad19)") (class "Default")
      (node (ref "IC4") (pin "19") (pinfunction "RESERVED_19") (pintype "bidirectional"))
      (node (ref "R34") (pin "1") (pinfunction "1_1") (pintype "passive"))
    )
    (net (code "123") (name "Net-(IC4E-DCDC_ANA_SW)") (class "Default")
      (node (ref "IC4") (pin "38") (pinfunction "DCDC_ANA_SW_38") (pintype "bidirectional"))
      (node (ref "L6") (pin "2") (pinfunction "2_2") (pintype "passive"))
    )
    (net (code "124") (name "Net-(IC4E-DCDC_DIG_SW)") (class "Default")
      (node (ref "IC4") (pin "43") (pinfunction "DCDC_DIG_SW_43") (pintype "bidirectional"))
      (node (ref "L4") (pin "2") (pinfunction "2_2") (pintype "passive"))
    )
    (net (code "125") (name "Net-(IC4E-DCDC_PA_OUT)") (class "Default")
      (node (ref "C27") (pin "2") (pinfunction "2_2") (pintype "passive"))
      (node (ref "C40") (pin "2") (pinfunction "2_2") (pintype "passive"))
      (node (ref "C55") (pin "2") (pinfunction "2_2") (pintype "passive"))
      (node (ref "IC4") (pin "33") (pinfunction "VDD_PA_IN_33") (pintype "bidirectional"))
      (node (ref "IC4") (pin "42") (pinfunction "DCDC_PA_OUT_42") (pintype "bidirectional"))
    )
    (net (code "126") (name "Net-(IC4E-DCDC_PA_SW_N)") (class "Default")
      (node (ref "IC4") (pin "41") (pinfunction "DCDC_PA_SW_N_41") (pintype "bidirectional"))
      (node (ref "L5") (pin "1") (pinfunction "1_1") (pintype "passive"))
    )
    (net (code "127") (name "Net-(IC4E-DCDC_PA_SW_P)") (class "Default")
      (node (ref "IC4") (pin "40") (pinfunction "DCDC_PA_SW_P_40") (pintype "bidirectional"))
      (node (ref "L5") (pin "2") (pinfunction "2_2") (pintype "passive"))
    )
    (net (code "128") (name "Net-(IC4E-LDO_IN1)") (class "Default")
      (node (ref "C36") (pin "2") (pinfunction "2_2") (pintype "passive"))
      (node (ref "C49") (pin "2") (pinfunction "2_2") (pintype "passive"))
      (node (ref "C50") (pin "2") (pinfunction "2_2") (pintype "passive"))
      (node (ref "C56") (pin "2") (pinfunction "2_2") (pintype "passive"))
      (node (ref "IC4") (pin "25") (pinfunction "LDO_IN2_25") (pintype "bidirectional"))
      (node (ref "IC4") (pin "36") (pinfunction "LDO_IN1_36") (pintype "bidirectional"))
      (node (ref "IC4") (pin "48") (pinfunction "VDD_ANA1_48") (pintype "bidirectional"))
      (node (ref "L6") (pin "1") (pinfunction "1_1") (pintype "passive"))
    )
    (net (code "129") (name "Net-(IC4E-VDD_DIG1)") (class "Default")
      (node (ref "C28") (pin "2") (pinfunction "2_2") (pintype "passive"))
      (node (ref "C30") (pin "2") (pinfunction "2_2") (pintype "passive"))
      (node (ref "C42") (pin "2") (pinfunction "2_2") (pintype "passive"))
      (node (ref "IC4") (pin "56") (pinfunction "VDD_DIG2_56") (pintype "bidirectional"))
      (node (ref "IC4") (pin "9") (pinfunction "VDD_DIG1_9") (pintype "bidirectional"))
      (node (ref "L4") (pin "1") (pinfunction "1_1") (pintype "passive"))
    )
    (net (code "130") (name "Net-(IC4E-VDD_PLL)") (class "Default")
      (node (ref "C62") (pin "2") (pinfunction "2_2") (pintype "passive"))
      (node (ref "IC4") (pin "24") (pinfunction "VDD_PLL_24") (pintype "bidirectional"))
    )
    (net (code "131") (name "Net-(IC4E-VDD_RAM)") (class "Default")
      (node (ref "C32") (pin "2") (pinfunction "2_2") (pintype "passive"))
      (node (ref "IC4") (pin "49") (pinfunction "VDD_RAM_49") (pintype "bidirectional"))
    )
    (net (code "132") (name "Net-(IC4F-TX)") (class "Default")
      (node (ref "IC4") (pin "55") (pinfunction "TX_55") (pintype "bidirectional"))
      (node (ref "R46") (pin "2") (pinfunction "2_2") (pintype "passive"))
      (node (ref "SV1") (pin "3") (pinfunction "3_3") (pintype "passive"))
    )
    (net (code "133") (name "Net-(IC4G-RCT_XTAL_N)") (class "Default")
      (node (ref "C26") (pin "2") (pinfunction "2_2") (pintype "passive"))
      (node (ref "IC4") (pin "52") (pinfunction "RCT_XTAL_N_52") (pintype "bidirectional"))
      (node (ref "R26") (pin "2") (pinfunction "2_2") (pintype "passive"))
      (node (ref "X4") (pin "P$1") (pinfunction "1_P$1") (pintype "bidirectional"))
    )
    (net (code "134") (name "Net-(IC4G-RTC_XTAL_P)") (class "Default")
      (node (ref "C25") (pin "2") (pinfunction "2_2") (pintype "passive"))
      (node (ref "IC4") (pin "51") (pinfunction "RTC_XTAL_P_51") (pintype "bidirectional"))
      (node (ref "R24") (pin "2") (pinfunction "2_2") (pintype "passive"))
      (node (ref "X4") (pin "P$2") (pinfunction "2_P$2") (pintype "bidirectional"))
    )
    (net (code "135") (name "Net-(IC4G-WLAN_XTAL_N)") (class "Default")
      (node (ref "C65") (pin "2") (pinfunction "2_2") (pintype "passive"))
      (node (ref "IC4") (pin "22") (pinfunction "WLAN_XTAL_N_22") (pintype "bidirectional"))
      (node (ref "X5") (pin "3") (pinfunction "C2_3") (pintype "passive"))
    )
    (net (code "136") (name "Net-(IC4G-WLAN_XTAL_P)") (class "Default")
      (node (ref "C68") (pin "2") (pinfunction "2_2") (pintype "passive"))
      (node (ref "IC4") (pin "23") (pinfunction "WLAN_XTAL_P_23") (pintype "bidirectional"))
      (node (ref "X5") (pin "1") (pinfunction "C1_1") (pintype "passive"))
    )
    (net (code "137") (name "Net-(J1-PadD+)") (class "Default")
      (node (ref "J1") (pin "D+") (pinfunction "D+_D+") (pintype "bidirectional"))
      (node (ref "R25") (pin "2") (pinfunction "2_2") (pintype "passive"))
      (node (ref "Z3") (pin "1") (pinfunction "1_1") (pintype "passive"))
    )
    (net (code "138") (name "Net-(J1-PadD-)") (class "Default")
      (node (ref "J1") (pin "D-") (pinfunction "D-_D-") (pintype "bidirectional"))
      (node (ref "R23") (pin "2") (pinfunction "2_2") (pintype "passive"))
      (node (ref "Z2") (pin "1") (pinfunction "1_1") (pintype "passive"))
    )
    (net (code "139") (name "Net-(J1-PadVBUS)") (class "Default")
      (node (ref "J1") (pin "VBUS") (pinfunction "VBUS_VBUS") (pintype "bidirectional"))
      (node (ref "L2") (pin "1") (pinfunction "1_1") (pintype "passive"))
    )
    (net (code "140") (name "Net-(LED1-PadA)") (class "Default")
      (node (ref "LED1") (pin "A") (pinfunction "A_A") (pintype "passive"))
      (node (ref "R1") (pin "1") (pinfunction "1_1") (pintype "passive"))
    )
    (net (code "141") (name "Net-(LED2-PadA)") (class "Default")
      (node (ref "LED2") (pin "A") (pinfunction "A_A") (pintype "passive"))
      (node (ref "R12") (pin "1") (pinfunction "1_1") (pintype "passive"))
    )
    (net (code "142") (name "Net-(LED3-PadA)") (class "Default")
      (node (ref "LED3") (pin "A") (pinfunction "A_A") (pintype "passive"))
      (node (ref "R14") (pin "1") (pinfunction "1_1") (pintype "passive"))
    )
    (net (code "143") (name "Net-(LED5-PadA)") (class "Default")
      (node (ref "LED5") (pin "A") (pinfunction "A_A") (pintype "passive"))
      (node (ref "R2") (pin "1") (pinfunction "1_1") (pintype "passive"))
    )
    (net (code "144") (name "Net-(Q1-B1)") (class "Default")
      (node (ref "Q1") (pin "1") (pinfunction "C1_1") (pintype "passive"))
      (node (ref "Q1") (pin "2") (pinfunction "B1_2") (pintype "passive"))
      (node (ref "Q1") (pin "3") (pinfunction "B2_3") (pintype "passive"))
      (node (ref "R16") (pin "1") (pinfunction "1_1") (pintype "passive"))
    )
    (net (code "145") (name "Net-(Q1-C2)") (class "Default")
      (node (ref "Q1") (pin "4") (pinfunction "C2_4") (pintype "passive"))
      (node (ref "Q2") (pin "1") (pinfunction "G_1") (pintype "bidirectional"))
      (node (ref "R15") (pin "1") (pinfunction "1_1") (pintype "passive"))
    )
    (net (code "146") (name "Net-(Q1-E2)") (class "Default")
      (node (ref "D3") (pin "C") (pinfunction "C_C") (pintype "passive"))
      (node (ref "Q1") (pin "5") (pinfunction "E2_5") (pintype "passive"))
      (node (ref "Q2") (pin "2") (pinfunction "S_2") (pintype "bidirectional"))
      (node (ref "Q6") (pin "2") (pinfunction "S_2") (pintype "bidirectional"))
      (node (ref "R45") (pin "1") (pinfunction "1_1") (pintype "passive"))
    )
    (net (code "147") (name "Net-(Q3-D)") (class "Default")
      (node (ref "Q3") (pin "3") (pinfunction "D_3") (pintype "bidirectional"))
      (node (ref "R32") (pin "2") (pinfunction "2_2") (pintype "passive"))
    )
    (net (code "148") (name "Net-(Q4-S)") (class "Default")
      (node (ref "Q4") (pin "2") (pinfunction "S_2") (pintype "bidirectional"))
      (node (ref "R44") (pin "2") (pinfunction "2_2") (pintype "passive"))
      (node (ref "TP13") (pin "TP") (pinfunction "TP_TP") (pintype "input"))
    )
    (net (code "149") (name "Net-(Q5-D)") (class "Default")
      (node (ref "Q5") (pin "3") (pinfunction "D_3") (pintype "bidirectional"))
      (node (ref "R1") (pin "2") (pinfunction "2_2") (pintype "passive"))
    )
    (net (code "150") (name "Net-(Q6-G)") (class "Default")
      (node (ref "Q6") (pin "1") (pinfunction "G_1") (pintype "bidirectional"))
      (node (ref "R45") (pin "2") (pinfunction "2_2") (pintype "passive"))
      (node (ref "S5") (pin "3") (pinfunction "S_3") (pintype "passive"))
    )
    (net (code "151") (name "Net-(R32-Pad1)") (class "Default")
      (node (ref "R32") (pin "1") (pinfunction "1_1") (pintype "passive"))
      (node (ref "U1") (pin "A") (pinfunction "A_A") (pintype "bidirectional"))
    )
    (net (code "152") (name "Net-(R41-Pad1)") (class "Default")
      (node (ref "R41") (pin "1") (pinfunction "1_1") (pintype "passive"))
      (node (ref "X6") (pin "1") (pinfunction "1_1") (pintype "passive"))
    )
    (net (code "153") (name "Net-(U3-PROG)") (class "Default")
      (node (ref "R6") (pin "1") (pinfunction "1_1") (pintype "passive"))
      (node (ref "U3") (pin "5") (pinfunction "PROG_5") (pintype "input"))
    )
    (net (code "154") (name "Net-(U3-STAT)") (class "Default")
      (node (ref "LED5") (pin "C") (pinfunction "C_C") (pintype "passive"))
      (node (ref "U3") (pin "1") (pinfunction "STAT_1") (pintype "output"))
    )
    (net (code "155") (name "Net-(X1-GPIO2)") (class "Default")
      (node (ref "R29") (pin "2") (pinfunction "2_2") (pintype "passive"))
      (node (ref "X1") (pin "11") (pinfunction "GPIO2_11") (pintype "bidirectional"))
    )
    (net (code "156") (name "Net-(X1-GPIO15)") (class "Default")
      (node (ref "R30") (pin "2") (pinfunction "2_2") (pintype "passive"))
      (node (ref "X1") (pin "10") (pinfunction "GPIO15_10") (pintype "bidirectional"))
    )
    (net (code "157") (name "Net-(X1-VCC)") (class "Default")
      (node (ref "C41") (pin "2") (pinfunction "2_2") (pintype "passive"))
      (node (ref "R13") (pin "2") (pinfunction "2_2") (pintype "passive"))
      (node (ref "TP14") (pin "TP") (pinfunction "TP_TP") (pintype "input"))
      (node (ref "X1") (pin "8") (pinfunction "VCC_8") (pintype "power_in"))
    )
    (net (code "158") (name "Net-(X2-C1)") (class "Default")
      (node (ref "C20") (pin "2") (pinfunction "2_2") (pintype "passive"))
      (node (ref "R43") (pin "2") (pinfunction "2_2") (pintype "passive"))
      (node (ref "X2") (pin "1") (pinfunction "C1_1") (pintype "passive"))
    )
    (net (code "159") (name "VBAT") (class "Default")
      (node (ref "C3") (pin "2") (pinfunction "2_2") (pintype "passive"))
      (node (ref "JP3") (pin "2") (pinfunction "2_2") (pintype "passive"))
      (node (ref "Q1") (pin "6") (pinfunction "E1_6") (pintype "passive"))
      (node (ref "Q2") (pin "3") (pinfunction "D_3") (pintype "bidirectional"))
      (node (ref "R21") (pin "2") (pinfunction "2_2") (pintype "passive"))
      (node (ref "U3") (pin "3") (pinfunction "VBAT_3") (pintype "power_in"))
    )
    (net (code "160") (name "unconnected-(IC3B-PB12-Pad51)") (class "Default")
      (node (ref "IC3") (pin "51") (pinfunction "PB12_51") (pintype "bidirectional"))
    )
    (net (code "161") (name "unconnected-(IC3E-PE2-Pad1)") (class "Default")
      (node (ref "IC3") (pin "1") (pinfunction "PE2_1") (pintype "bidirectional"))
    )
    (net (code "162") (name "unconnected-(IC3E-PE12-Pad43)") (class "Default")
      (node (ref "IC3") (pin "43") (pinfunction "PE12_43") (pintype "bidirectional"))
    )
    (net (code "163") (name "unconnected-(IC4B-RESERVED-Pad29)") (class "Default")
      (node (ref "IC4") (pin "29") (pinfunction "RESERVED_29") (pintype "bidirectional"))
    )
    (net (code "164") (name "unconnected-(IC4B-RESERVED-Pad30)") (class "Default")
      (node (ref "IC4") (pin "30") (pinfunction "RESERVED_30") (pintype "bidirectional"))
    )
    (net (code "165") (name "unconnected-(IC4B-TEST-Pad58)") (class "Default")
      (node (ref "IC4") (pin "58") (pinfunction "TEST_58") (pintype "bidirectional"))
    )
    (net (code "166") (name "unconnected-(IC4B-TEST-Pad59)") (class "Default")
      (node (ref "IC4") (pin "59") (pinfunction "TEST_59") (pintype "bidirectional"))
    )
    (net (code "167") (name "unconnected-(IC4B-TEST-Pad60)") (class "Default")
      (node (ref "IC4") (pin "60") (pinfunction "TEST_60") (pintype "bidirectional"))
    )
    (net (code "168") (name "unconnected-(IC4B-TEST-Pad62)") (class "Default")
      (node (ref "IC4") (pin "62") (pinfunction "TEST_62") (pintype "bidirectional"))
    )
    (net (code "169") (name "unconnected-(IC4E-DCDC_ANA2_SW_N-Pad46)") (class "Default")
      (node (ref "IC4") (pin "46") (pinfunction "DCDC_ANA2_SW_N_46") (pintype "bidirectional"))
    )
    (net (code "170") (name "unconnected-(IC4E-DCDC_ANA2_SW_P-Pad45)") (class "Default")
      (node (ref "IC4") (pin "45") (pinfunction "DCDC_ANA2_SW_P_45") (pintype "bidirectional"))
    )
    (net (code "171") (name "unconnected-(IC4E-VDD_ANA2-Pad47)") (class "Default")
      (node (ref "IC4") (pin "47") (pinfunction "VDD_ANA2_47") (pintype "bidirectional"))
    )
    (net (code "172") (name "unconnected-(IC4F-~{CTS}-Pad61)") (class "Default")
      (node (ref "IC4") (pin "61") (pinfunction "~{CTS}_61") (pintype "bidirectional"))
    )
    (net (code "173") (name "unconnected-(IC4F-~{RTS}-Pad50)") (class "Default")
      (node (ref "IC4") (pin "50") (pinfunction "~{RTS}_50") (pintype "bidirectional"))
    )
    (net (code "174") (name "unconnected-(J2-NC-Pad1)") (class "Default")
      (node (ref "J2") (pin "1") (pinfunction "NC_1") (pintype "bidirectional"))
    )
    (net (code "175") (name "unconnected-(J2-NC-Pad30)") (class "Default")
      (node (ref "J2") (pin "30") (pinfunction "NC_30") (pintype "bidirectional"))
    )
    (net (code "176") (name "unconnected-(J3-KEY-Pad7)") (class "Default")
      (node (ref "J3") (pin "7") (pinfunction "KEY_7") (pintype "bidirectional"))
    )
    (net (code "177") (name "unconnected-(J3-NC-Pad8)") (class "Default")
      (node (ref "J3") (pin "8") (pinfunction "NC_8") (pintype "no_connect"))
    )
    (net (code "178") (name "unconnected-(J3-SWO-Pad6)") (class "Default")
      (node (ref "J3") (pin "6") (pinfunction "SWO_6") (pintype "bidirectional"))
    )
    (net (code "179") (name "unconnected-(S5-O-Pad1)") (class "Default")
      (node (ref "S5") (pin "1") (pinfunction "O_1") (pintype "passive"))
    )
    (net (code "180") (name "unconnected-(U2-PadRESERVED)") (class "Default")
      (node (ref "U2") (pin "RESERVED") (pinfunction "RESERVED_RESERVED") (pintype "no_connect"))
    )
    (net (code "181") (name "unconnected-(X1-ADC-Pad2)") (class "Default")
      (node (ref "X1") (pin "2") (pinfunction "ADC_2") (pintype "bidirectional"))
    )
    (net (code "182") (name "unconnected-(X1-GPIO4-Pad14)") (class "Default")
      (node (ref "X1") (pin "14") (pinfunction "GPIO4_14") (pintype "bidirectional"))
    )
    (net (code "183") (name "unconnected-(X1-GPIO5-Pad13)") (class "Default")
      (node (ref "X1") (pin "13") (pinfunction "GPIO5_13") (pintype "bidirectional"))
    )
    (net (code "184") (name "unconnected-(X1-GPIO12-Pad6)") (class "Default")
      (node (ref "X1") (pin "6") (pinfunction "GPIO12_6") (pintype "bidirectional"))
    )
    (net (code "185") (name "unconnected-(X1-GPIO13-Pad7)") (class "Default")
      (node (ref "X1") (pin "7") (pinfunction "GPIO13_7") (pintype "bidirectional"))
    )
    (net (code "186") (name "unconnected-(X1-GPIO14-Pad5)") (class "Default")
      (node (ref "X1") (pin "5") (pinfunction "GPIO14_5") (pintype "bidirectional"))
    )
    (net (code "187") (name "unconnected-(X1-REST-Pad1)") (class "Default")
      (node (ref "X1") (pin "1") (pinfunction "REST_1") (pintype "input"))
    )
  )
)
